# tp34.net
KiCad netlist of a schematic drawn in EAGLE
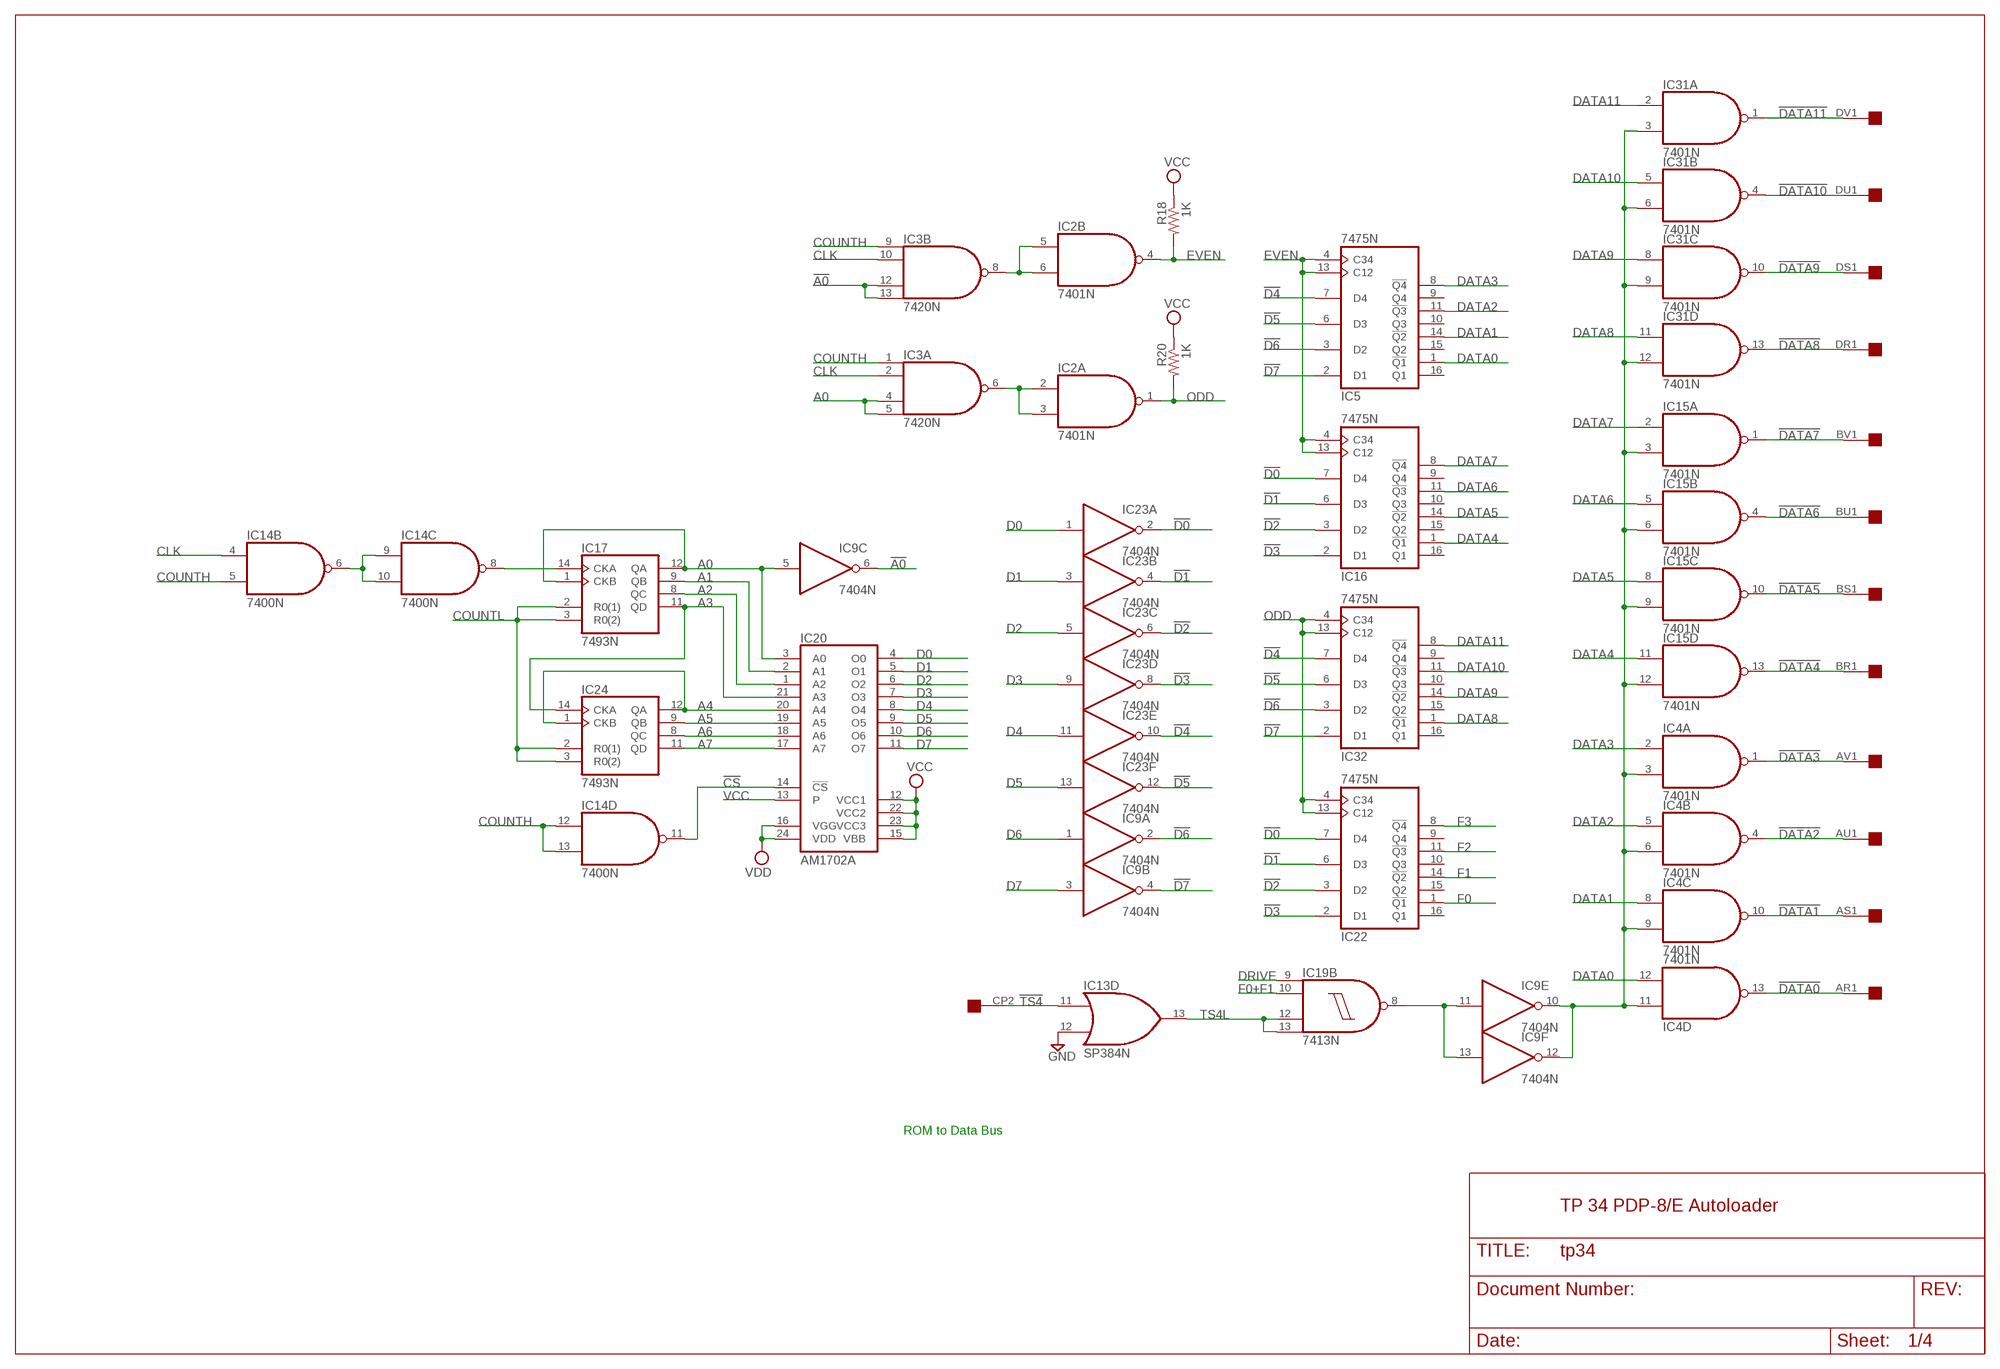
[diagram p0: schematic, sheet 1]
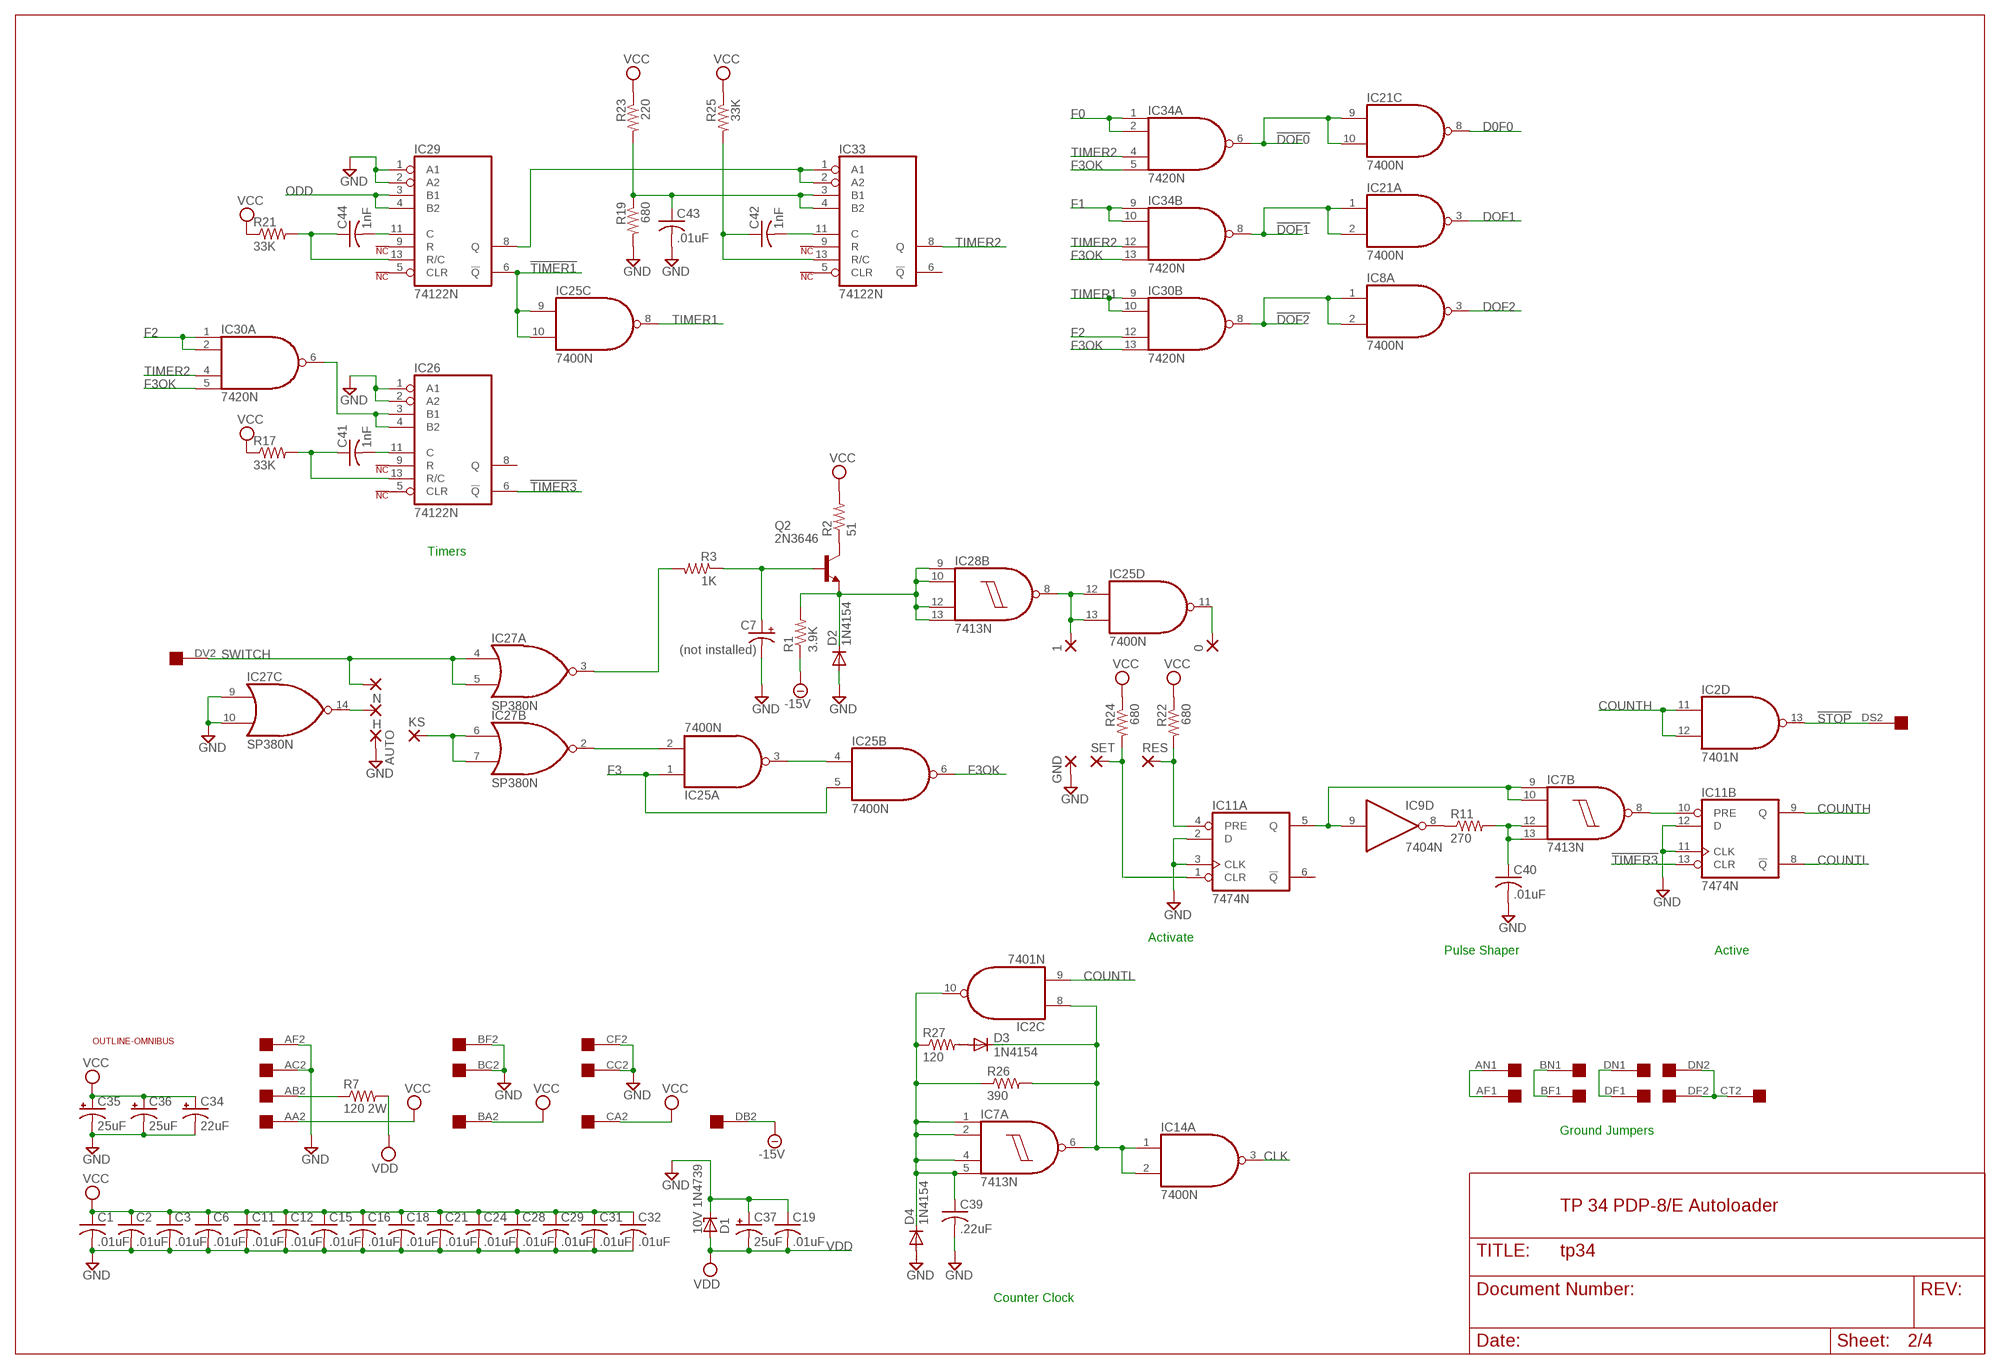
[diagram p1: schematic, sheet 2]
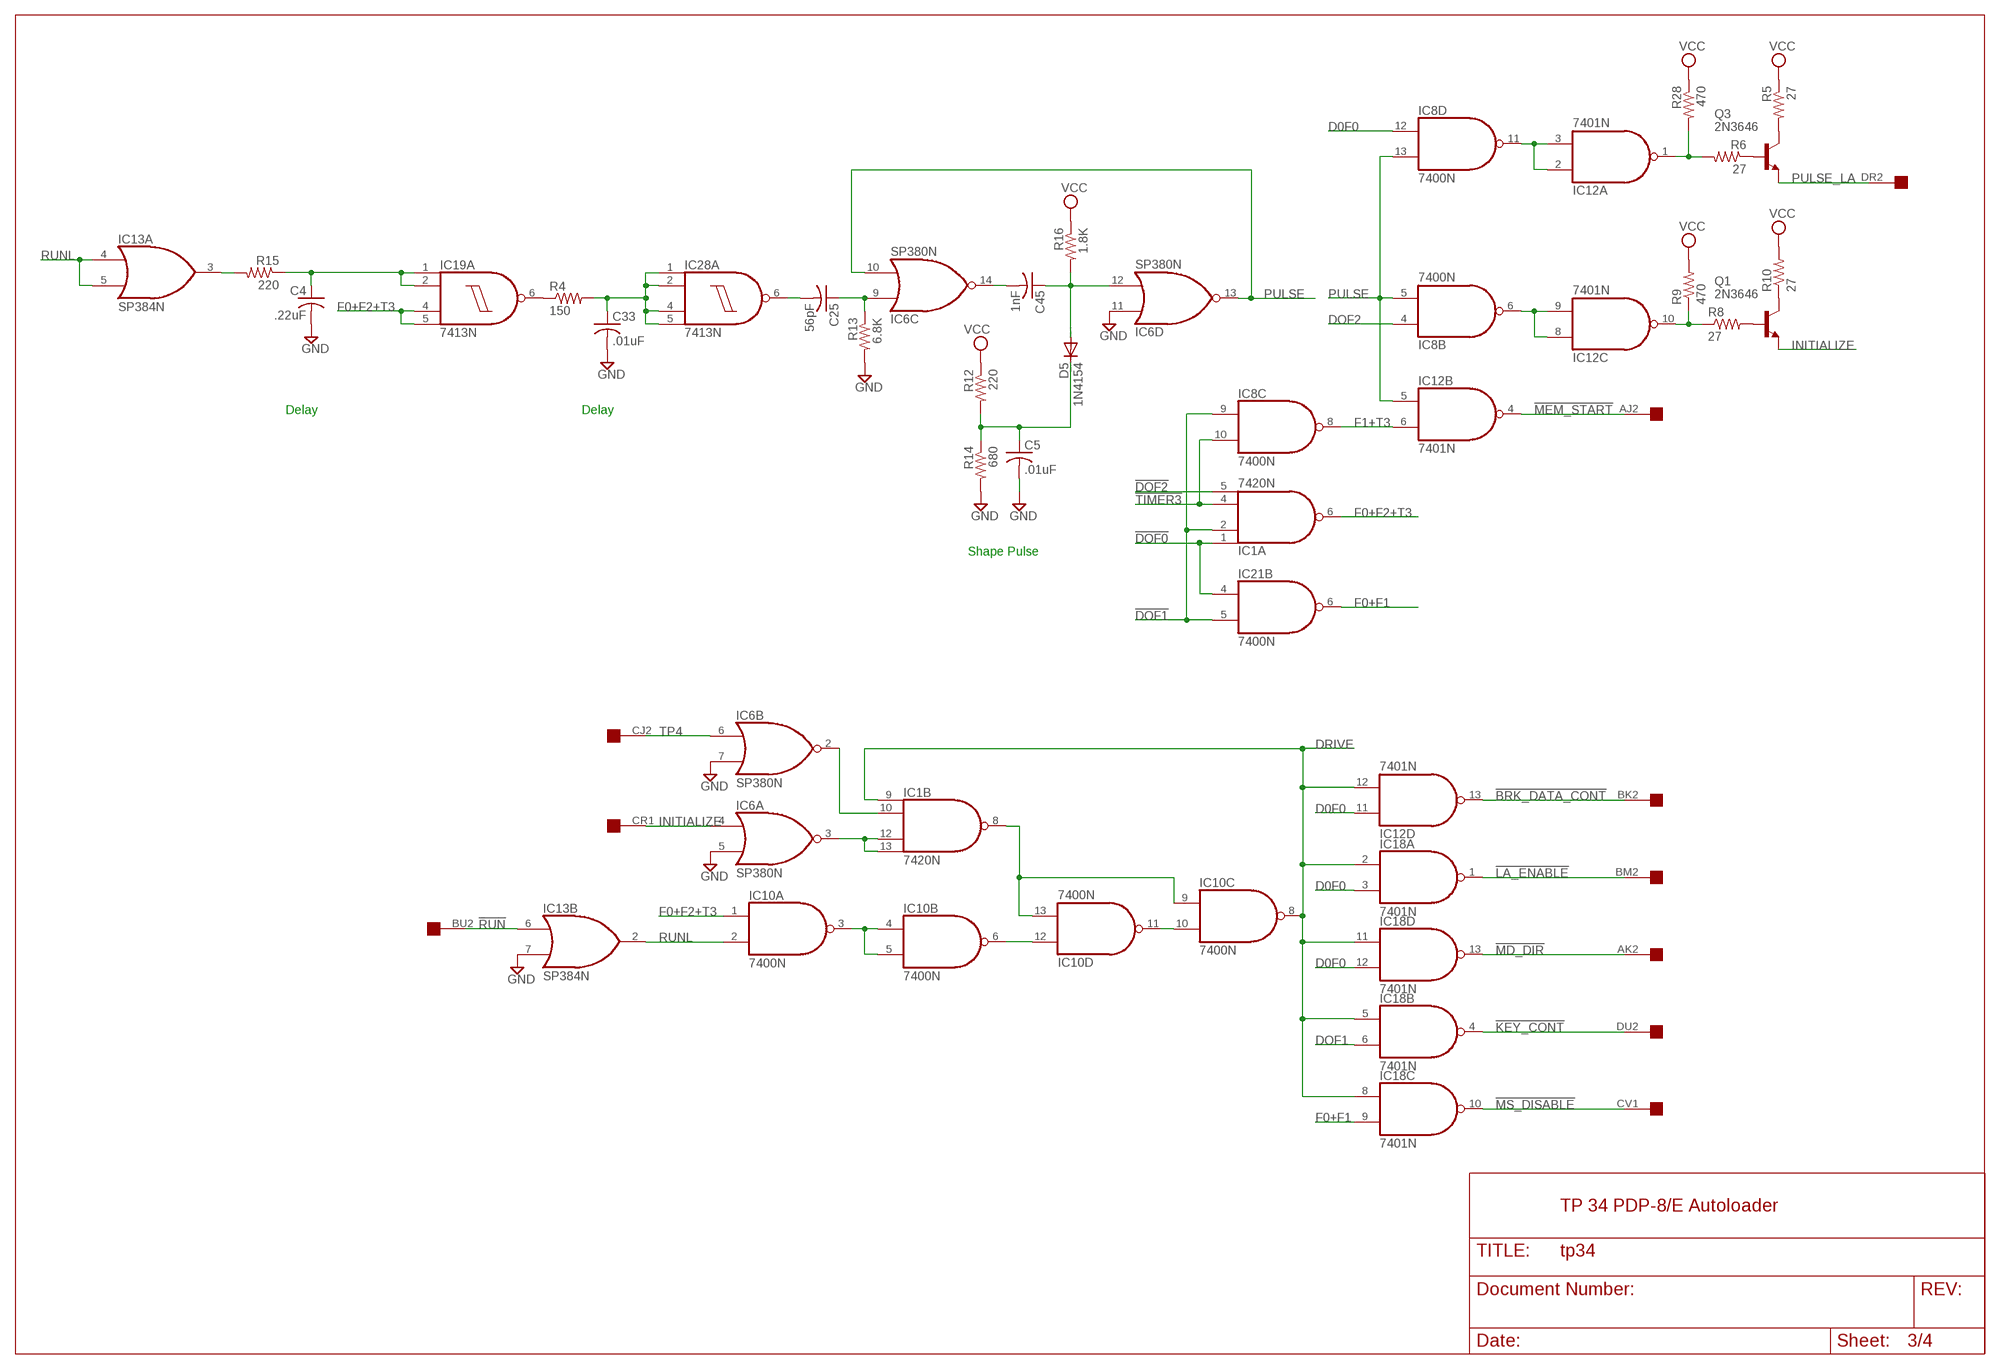
[diagram p2: schematic, sheet 3]
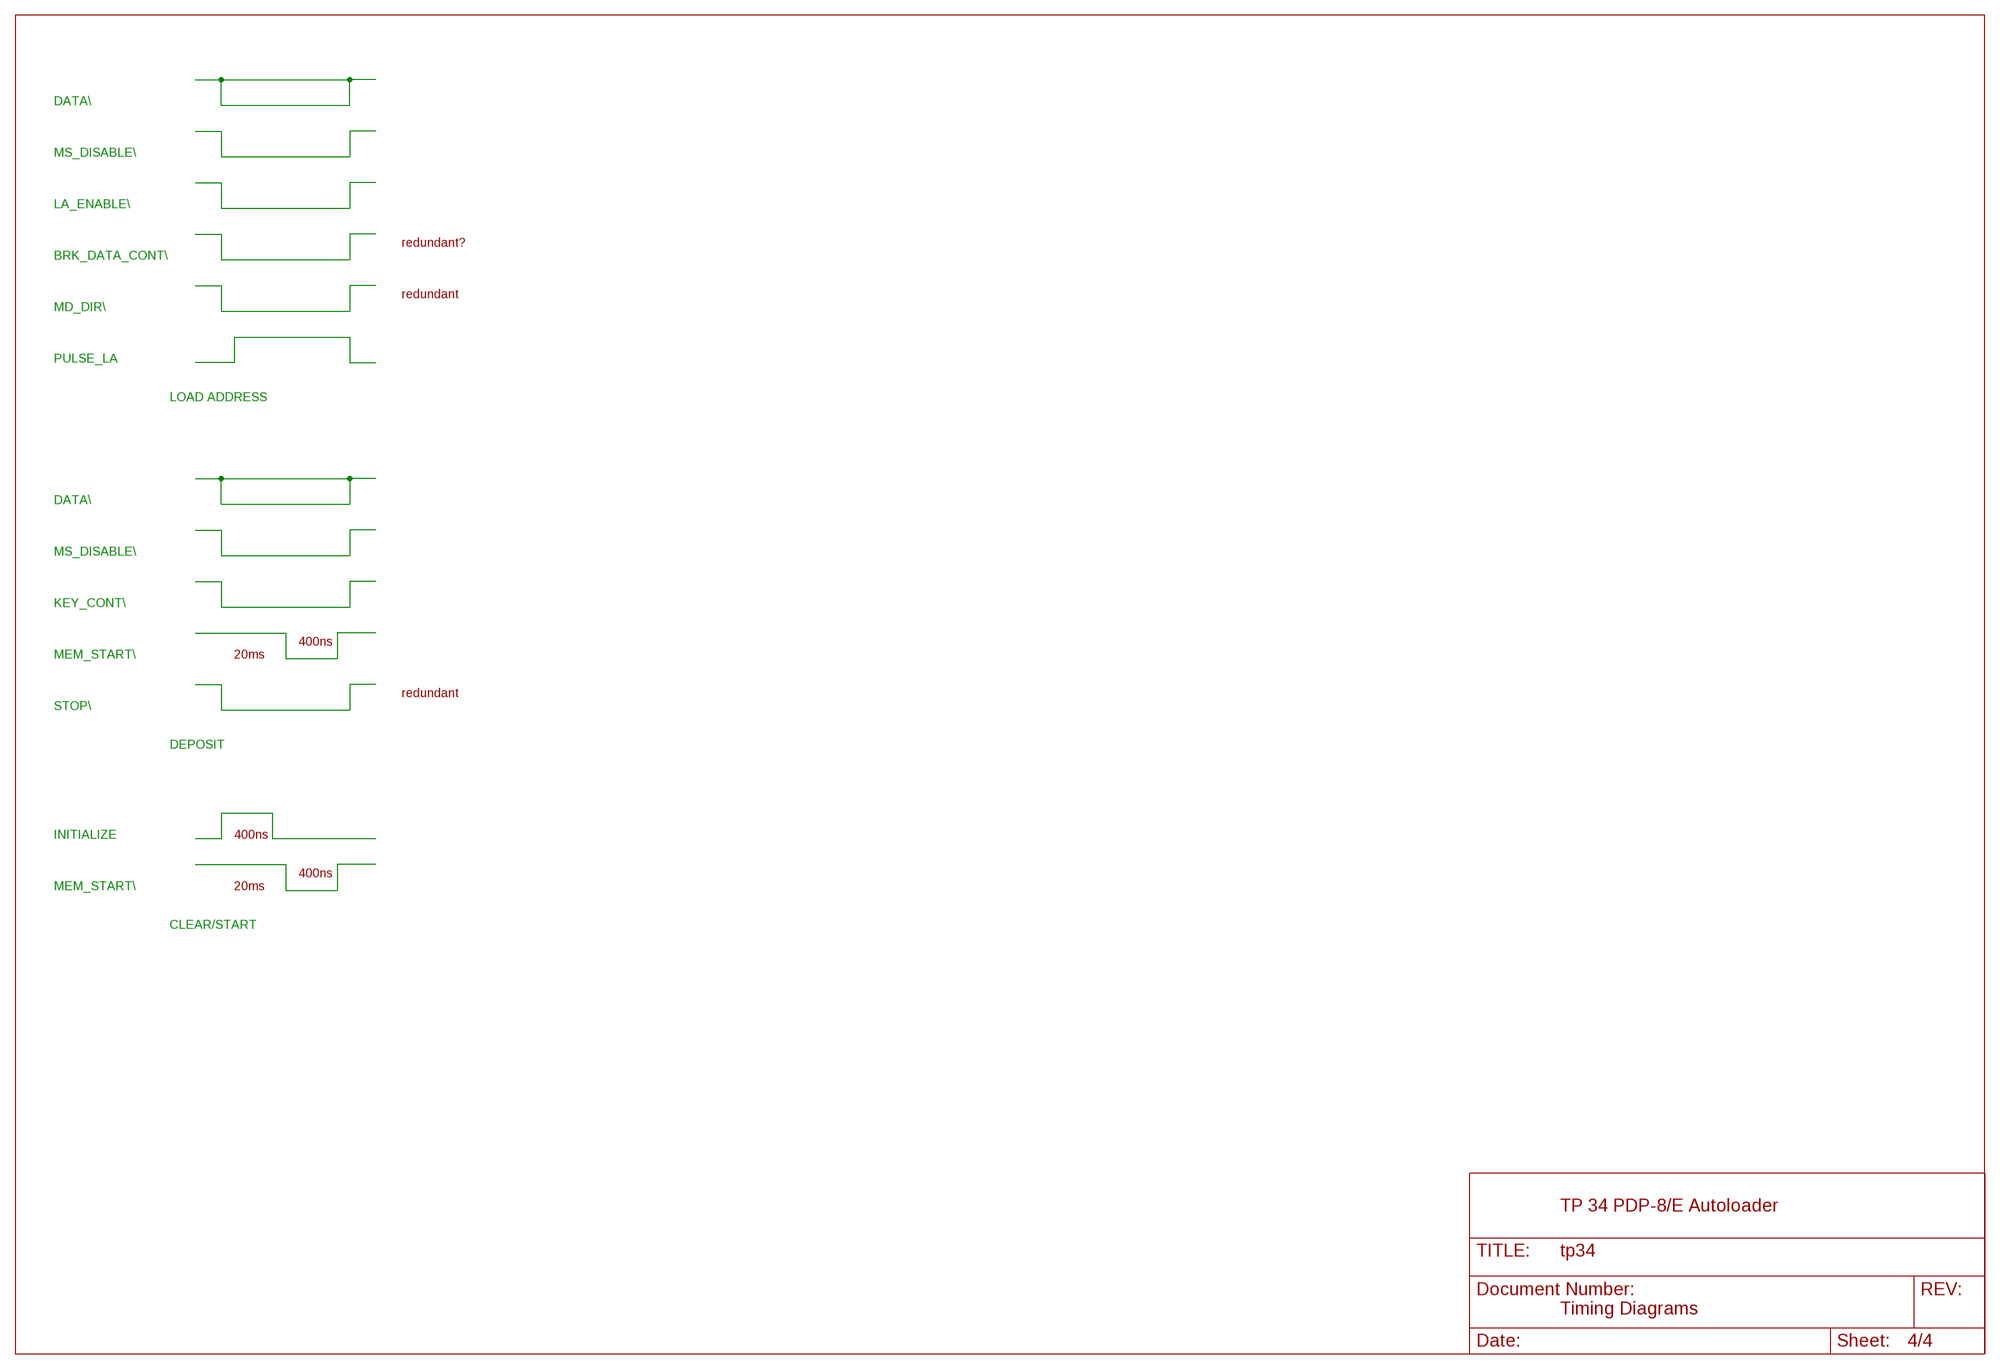
[diagram p3: schematic, sheet 4]

(export (version "E")
  (design (tool "Eeschema 10.0.6"))
  (components
    (comp (ref "IC2")
      (value "7401N")
      (footprint "eagle-import:DIL14")
      (libsource (lib "eagle-import") (part "7401NLS"))
    )
    (comp (ref "IC3")
      (value "7420N")
      (footprint "eagle-import:DIL14")
      (libsource (lib "eagle-import") (part "7420NS"))
    )
    (comp (ref "IC4")
      (value "7401N")
      (footprint "eagle-import:DIL14")
      (libsource (lib "eagle-import") (part "7401NLS"))
    )
    (comp (ref "IC5")
      (value "7475N")
      (footprint "eagle-import:DIL16")
      (libsource (lib "eagle-import") (part "7475N"))
    )
    (comp (ref "IC9")
      (value "7404N")
      (footprint "eagle-import:DIL14")
      (libsource (lib "eagle-import") (part "7404N"))
    )
    (comp (ref "IC13")
      (value "SP384N")
      (footprint "eagle-import:DIL14")
      (libsource (lib "eagle-import") (part "SP384N"))
    )
    (comp (ref "IC14")
      (value "7400N")
      (footprint "eagle-import:DIL14")
      (libsource (lib "eagle-import") (part "7400N"))
    )
    (comp (ref "IC15")
      (value "7401N")
      (footprint "eagle-import:DIL14")
      (libsource (lib "eagle-import") (part "7401NLS"))
    )
    (comp (ref "IC16")
      (value "7475N")
      (footprint "eagle-import:DIL16")
      (libsource (lib "eagle-import") (part "7475N"))
    )
    (comp (ref "IC17")
      (value "7493N")
      (footprint "eagle-import:DIL14")
      (libsource (lib "eagle-import") (part "7493NLS"))
    )
    (comp (ref "IC19")
      (value "7413N")
      (footprint "eagle-import:DIL14")
      (libsource (lib "eagle-import") (part "7413N"))
    )
    (comp (ref "IC20")
      (value "AM1702A")
      (footprint "eagle-import:DIL24")
      (libsource (lib "eagle-import") (part "AM1702"))
    )
    (comp (ref "IC22")
      (value "7475N")
      (footprint "eagle-import:DIL16")
      (libsource (lib "eagle-import") (part "7475N"))
    )
    (comp (ref "IC23")
      (value "7404N")
      (footprint "eagle-import:DIL14")
      (libsource (lib "eagle-import") (part "7404N"))
    )
    (comp (ref "IC24")
      (value "7493N")
      (footprint "eagle-import:DIL14")
      (libsource (lib "eagle-import") (part "7493NLS"))
    )
    (comp (ref "IC31")
      (value "7401N")
      (footprint "eagle-import:DIL14")
      (libsource (lib "eagle-import") (part "7401NLS"))
    )
    (comp (ref "IC32")
      (value "7475N")
      (footprint "eagle-import:DIL16")
      (libsource (lib "eagle-import") (part "7475N"))
    )
    (comp (ref "R18")
      (value "1K")
      (footprint "eagle-import:0207_10")
      (libsource (lib "eagle-import") (part "R-US_0207/10"))
    )
    (comp (ref "R20")
      (value "1K")
      (footprint "eagle-import:0207_10")
      (libsource (lib "eagle-import") (part "R-US_0207/10"))
    )
    (comp (ref "U$2")
      (value "QUAD")
      (footprint "eagle-import:EDGE-CON8")
      (libsource (lib "eagle-import") (part "QUAD"))
    )
    (comp (ref "C4")
      (value ".22uF")
      (footprint "eagle-import:C075-032X103")
      (libsource (lib "eagle-import") (part "C-US075-032X103"))
    )
    (comp (ref "C5")
      (value ".01uF")
      (footprint "eagle-import:C075-032X103")
      (libsource (lib "eagle-import") (part "C-US075-032X103"))
    )
    (comp (ref "C25")
      (value "56pF")
      (footprint "eagle-import:C102-043X133")
      (libsource (lib "eagle-import") (part "C-US102-043X133"))
    )
    (comp (ref "C33")
      (value ".01uF")
      (footprint "eagle-import:C075-032X103")
      (libsource (lib "eagle-import") (part "C-US075-032X103"))
    )
    (comp (ref "C45")
      (value "1nF")
      (footprint "eagle-import:C050-035X075")
      (libsource (lib "eagle-import") (part "C-US050-035X075"))
    )
    (comp (ref "D5")
      (value "1N4154")
      (footprint "eagle-import:DO35-10")
      (libsource (lib "eagle-import") (part "1N4148DO35-10"))
    )
    (comp (ref "IC1")
      (value "7420N")
      (footprint "eagle-import:DIL14")
      (libsource (lib "eagle-import") (part "7420NS"))
    )
    (comp (ref "IC6")
      (value "SP380N")
      (footprint "eagle-import:DIL14")
      (libsource (lib "eagle-import") (part "SP380N"))
    )
    (comp (ref "IC8")
      (value "7400N")
      (footprint "eagle-import:DIL14")
      (libsource (lib "eagle-import") (part "7400N"))
    )
    (comp (ref "IC10")
      (value "7400N")
      (footprint "eagle-import:DIL14")
      (libsource (lib "eagle-import") (part "7400N"))
    )
    (comp (ref "IC12")
      (value "7401N")
      (footprint "eagle-import:DIL14")
      (libsource (lib "eagle-import") (part "7401NLS"))
    )
    (comp (ref "IC18")
      (value "7401N")
      (footprint "eagle-import:DIL14")
      (libsource (lib "eagle-import") (part "7401NLS"))
    )
    (comp (ref "IC21")
      (value "7400N")
      (footprint "eagle-import:DIL14")
      (libsource (lib "eagle-import") (part "7400N"))
    )
    (comp (ref "IC28")
      (value "7413N")
      (footprint "eagle-import:DIL14")
      (libsource (lib "eagle-import") (part "7413N"))
    )
    (comp (ref "Q1")
      (value "2N3646")
      (footprint "eagle-import:TO5")
      (libsource (lib "eagle-import") (part "2N2102"))
    )
    (comp (ref "Q3")
      (value "2N3646")
      (footprint "eagle-import:TO5")
      (libsource (lib "eagle-import") (part "2N2102"))
    )
    (comp (ref "R4")
      (value "150")
      (footprint "eagle-import:0207_10")
      (libsource (lib "eagle-import") (part "R-US_0207/10"))
    )
    (comp (ref "R5")
      (value "27")
      (footprint "eagle-import:0207_10")
      (libsource (lib "eagle-import") (part "R-US_0207/10"))
    )
    (comp (ref "R6")
      (value "27")
      (footprint "eagle-import:0207_10")
      (libsource (lib "eagle-import") (part "R-US_0207/10"))
    )
    (comp (ref "R8")
      (value "27")
      (footprint "eagle-import:0207_10")
      (libsource (lib "eagle-import") (part "R-US_0207/10"))
    )
    (comp (ref "R9")
      (value "470")
      (footprint "eagle-import:0207_10")
      (libsource (lib "eagle-import") (part "R-US_0207/10"))
    )
    (comp (ref "R10")
      (value "27")
      (footprint "eagle-import:0207_10")
      (libsource (lib "eagle-import") (part "R-US_0207/10"))
    )
    (comp (ref "R12")
      (value "220")
      (footprint "eagle-import:0207_10")
      (libsource (lib "eagle-import") (part "R-US_0207/10"))
    )
    (comp (ref "R13")
      (value "6.8K")
      (footprint "eagle-import:0207_10")
      (libsource (lib "eagle-import") (part "R-US_0207/10"))
    )
    (comp (ref "R14")
      (value "680")
      (footprint "eagle-import:0207_10")
      (libsource (lib "eagle-import") (part "R-US_0207/10"))
    )
    (comp (ref "R15")
      (value "220")
      (footprint "eagle-import:0207_15")
      (libsource (lib "eagle-import") (part "R-US_0207/15"))
    )
    (comp (ref "R16")
      (value "1.8K")
      (footprint "eagle-import:0207_10")
      (libsource (lib "eagle-import") (part "R-US_0207/10"))
    )
    (comp (ref "R28")
      (value "470")
      (footprint "eagle-import:0207_10")
      (libsource (lib "eagle-import") (part "R-US_0207/10"))
    )
    (comp (ref "0")
      (value "1,6/0,8")
      (footprint "eagle-import:1,6_0,8")
      (libsource (lib "eagle-import") (part "1,6/0,8"))
    )
    (comp (ref "1")
      (value "1,6/0,8")
      (footprint "eagle-import:1,6_0,8")
      (libsource (lib "eagle-import") (part "1,6/0,8"))
    )
    (comp (ref "AUTO")
      (value "1,6/0,8")
      (footprint "eagle-import:1,6_0,8")
      (libsource (lib "eagle-import") (part "1,6/0,8"))
    )
    (comp (ref "C1")
      (value ".01uF")
      (footprint "eagle-import:C075-032X103")
      (libsource (lib "eagle-import") (part "C-US075-032X103"))
    )
    (comp (ref "C2")
      (value ".01uF")
      (footprint "eagle-import:C075-032X103")
      (libsource (lib "eagle-import") (part "C-US075-032X103"))
    )
    (comp (ref "C3")
      (value ".01uF")
      (footprint "eagle-import:C075-032X103")
      (libsource (lib "eagle-import") (part "C-US075-032X103"))
    )
    (comp (ref "C6")
      (value ".01uF")
      (footprint "eagle-import:C075-032X103")
      (libsource (lib "eagle-import") (part "C-US075-032X103"))
    )
    (comp (ref "C7")
      (value "(not installed)")
      (footprint "eagle-import:E15-5")
      (libsource (lib "eagle-import") (part "CPOL-USE15-5AXIAL"))
    )
    (comp (ref "C11")
      (value ".01uF")
      (footprint "eagle-import:C075-032X103")
      (libsource (lib "eagle-import") (part "C-US075-032X103"))
    )
    (comp (ref "C12")
      (value ".01uF")
      (footprint "eagle-import:C075-032X103")
      (libsource (lib "eagle-import") (part "C-US075-032X103"))
    )
    (comp (ref "C15")
      (value ".01uF")
      (footprint "eagle-import:C075-032X103")
      (libsource (lib "eagle-import") (part "C-US075-032X103"))
    )
    (comp (ref "C16")
      (value ".01uF")
      (footprint "eagle-import:C075-032X103")
      (libsource (lib "eagle-import") (part "C-US075-032X103"))
    )
    (comp (ref "C18")
      (value ".01uF")
      (footprint "eagle-import:C075-032X103")
      (libsource (lib "eagle-import") (part "C-US075-032X103"))
    )
    (comp (ref "C19")
      (value ".01uF")
      (footprint "eagle-import:C075-032X103")
      (libsource (lib "eagle-import") (part "C-US075-032X103"))
    )
    (comp (ref "C21")
      (value ".01uF")
      (footprint "eagle-import:C075-032X103")
      (libsource (lib "eagle-import") (part "C-US075-032X103"))
    )
    (comp (ref "C24")
      (value ".01uF")
      (footprint "eagle-import:C075-032X103")
      (libsource (lib "eagle-import") (part "C-US075-032X103"))
    )
    (comp (ref "C28")
      (value ".01uF")
      (footprint "eagle-import:C075-032X103")
      (libsource (lib "eagle-import") (part "C-US075-032X103"))
    )
    (comp (ref "C29")
      (value ".01uF")
      (footprint "eagle-import:C075-032X103")
      (libsource (lib "eagle-import") (part "C-US075-032X103"))
    )
    (comp (ref "C31")
      (value ".01uF")
      (footprint "eagle-import:C075-032X103")
      (libsource (lib "eagle-import") (part "C-US075-032X103"))
    )
    (comp (ref "C32")
      (value ".01uF")
      (footprint "eagle-import:C075-032X103")
      (libsource (lib "eagle-import") (part "C-US075-032X103"))
    )
    (comp (ref "C34")
      (value "22uF")
      (footprint "eagle-import:E12-8")
      (libsource (lib "eagle-import") (part "CPOL-USE20-8AXIAL"))
    )
    (comp (ref "C35")
      (value "25uF")
      (footprint "eagle-import:E15-5")
      (libsource (lib "eagle-import") (part "CPOL-USE15-5AXIAL"))
    )
    (comp (ref "C36")
      (value "25uF")
      (footprint "eagle-import:E15-5")
      (libsource (lib "eagle-import") (part "CPOL-USE15-5AXIAL"))
    )
    (comp (ref "C37")
      (value "25uF")
      (footprint "eagle-import:E15-5")
      (libsource (lib "eagle-import") (part "CPOL-USE15-5AXIAL"))
    )
    (comp (ref "C39")
      (value ".22uF")
      (footprint "eagle-import:C075-032X103")
      (libsource (lib "eagle-import") (part "C-US075-032X103"))
    )
    (comp (ref "C40")
      (value ".01uF")
      (footprint "eagle-import:C075-032X103")
      (libsource (lib "eagle-import") (part "C-US075-032X103"))
    )
    (comp (ref "C41")
      (value "1nF")
      (footprint "eagle-import:C075-032X103")
      (libsource (lib "eagle-import") (part "C-US075-032X103"))
    )
    (comp (ref "C42")
      (value "1nF")
      (footprint "eagle-import:C075-032X103")
      (libsource (lib "eagle-import") (part "C-US075-032X103"))
    )
    (comp (ref "C43")
      (value ".01uF")
      (footprint "eagle-import:C075-032X103")
      (libsource (lib "eagle-import") (part "C-US075-032X103"))
    )
    (comp (ref "C44")
      (value "1nF")
      (footprint "eagle-import:C075-032X103")
      (libsource (lib "eagle-import") (part "C-US075-032X103"))
    )
    (comp (ref "D1")
      (value "10V 1N4739")
      (footprint "eagle-import:C1702-15")
      (libsource (lib "eagle-import") (part "ZENER-DIODEC1702-15"))
    )
    (comp (ref "D2")
      (value "1N4154")
      (footprint "eagle-import:DO35-10")
      (libsource (lib "eagle-import") (part "1N4148DO35-10"))
    )
    (comp (ref "D3")
      (value "1N4154")
      (footprint "eagle-import:DO35-10")
      (libsource (lib "eagle-import") (part "1N4148DO35-10"))
    )
    (comp (ref "D4")
      (value "1N4154")
      (footprint "eagle-import:DO35-10")
      (libsource (lib "eagle-import") (part "1N4148DO35-10"))
    )
    (comp (ref "GND")
      (value "1,6/0,8")
      (footprint "eagle-import:1,6_0,8")
      (libsource (lib "eagle-import") (part "1,6/0,8"))
    )
    (comp (ref "H")
      (value "1,6/0,8")
      (footprint "eagle-import:1,6_0,8")
      (libsource (lib "eagle-import") (part "1,6/0,8"))
    )
    (comp (ref "IC7")
      (value "7413N")
      (footprint "eagle-import:DIL14")
      (libsource (lib "eagle-import") (part "7413N"))
    )
    (comp (ref "IC11")
      (value "7474N")
      (footprint "eagle-import:DIL14")
      (libsource (lib "eagle-import") (part "7474NS"))
    )
    (comp (ref "IC25")
      (value "7400N")
      (footprint "eagle-import:DIL14")
      (libsource (lib "eagle-import") (part "7400N"))
    )
    (comp (ref "IC26")
      (value "74122N")
      (footprint "eagle-import:DIL14")
      (libsource (lib "eagle-import") (part "74122NLS"))
    )
    (comp (ref "IC27")
      (value "SP380N")
      (footprint "eagle-import:DIL14")
      (libsource (lib "eagle-import") (part "SP380N"))
    )
    (comp (ref "IC29")
      (value "74122N")
      (footprint "eagle-import:DIL14")
      (libsource (lib "eagle-import") (part "74122NLS"))
    )
    (comp (ref "IC30")
      (value "7420N")
      (footprint "eagle-import:DIL14")
      (libsource (lib "eagle-import") (part "7420NS"))
    )
    (comp (ref "IC33")
      (value "74122N")
      (footprint "eagle-import:DIL14")
      (libsource (lib "eagle-import") (part "74122NLS"))
    )
    (comp (ref "IC34")
      (value "7420N")
      (footprint "eagle-import:DIL14")
      (libsource (lib "eagle-import") (part "7420NS"))
    )
    (comp (ref "KS")
      (value "1,6/0,8")
      (footprint "eagle-import:1,6_0,8")
      (libsource (lib "eagle-import") (part "1,6/0,8"))
    )
    (comp (ref "N")
      (value "1,6/0,8")
      (footprint "eagle-import:1,6_0,8")
      (libsource (lib "eagle-import") (part "1,6/0,8"))
    )
    (comp (ref "Q2")
      (value "2N3646")
      (footprint "eagle-import:TO5")
      (libsource (lib "eagle-import") (part "2N2102"))
    )
    (comp (ref "R1")
      (value "3.9K")
      (footprint "eagle-import:0207_10")
      (libsource (lib "eagle-import") (part "R-US_0207/10"))
    )
    (comp (ref "R2")
      (value "51")
      (footprint "eagle-import:0207_10")
      (libsource (lib "eagle-import") (part "R-US_0207/10"))
    )
    (comp (ref "R3")
      (value "1K")
      (footprint "eagle-import:0207_10")
      (libsource (lib "eagle-import") (part "R-US_0207/10"))
    )
    (comp (ref "R7")
      (value "120 2W")
      (footprint "eagle-import:0414_15")
      (libsource (lib "eagle-import") (part "R-US_0414/15"))
    )
    (comp (ref "R11")
      (value "270")
      (footprint "eagle-import:0207_12")
      (libsource (lib "eagle-import") (part "R-US_0207/12"))
    )
    (comp (ref "R17")
      (value "33K")
      (footprint "eagle-import:0207_10")
      (libsource (lib "eagle-import") (part "R-US_0207/10"))
    )
    (comp (ref "R19")
      (value "680")
      (footprint "eagle-import:0207_10")
      (libsource (lib "eagle-import") (part "R-US_0207/10"))
    )
    (comp (ref "R21")
      (value "33K")
      (footprint "eagle-import:0207_10")
      (libsource (lib "eagle-import") (part "R-US_0207/10"))
    )
    (comp (ref "R22")
      (value "680")
      (footprint "eagle-import:0207_10")
      (libsource (lib "eagle-import") (part "R-US_0207/10"))
    )
    (comp (ref "R23")
      (value "220")
      (footprint "eagle-import:0207_10")
      (libsource (lib "eagle-import") (part "R-US_0207/10"))
    )
    (comp (ref "R24")
      (value "680")
      (footprint "eagle-import:0207_10")
      (libsource (lib "eagle-import") (part "R-US_0207/10"))
    )
    (comp (ref "R25")
      (value "33K")
      (footprint "eagle-import:0207_10")
      (libsource (lib "eagle-import") (part "R-US_0207/10"))
    )
    (comp (ref "R26")
      (value "390")
      (footprint "eagle-import:0207_10")
      (libsource (lib "eagle-import") (part "R-US_0207/10"))
    )
    (comp (ref "R27")
      (value "120")
      (footprint "eagle-import:0207_10")
      (libsource (lib "eagle-import") (part "R-US_0207/10"))
    )
    (comp (ref "RES")
      (value "1,6/0,8")
      (footprint "eagle-import:1,6_0,8")
      (libsource (lib "eagle-import") (part "1,6/0,8"))
    )
    (comp (ref "SET")
      (value "1,6/0,8")
      (footprint "eagle-import:1,6_0,8")
      (libsource (lib "eagle-import") (part "1,6/0,8"))
    )
    (comp (ref "U$1")
      (value "OUTLINE-OMNIBUS")
      (footprint "eagle-import:OMNIBUS")
      (libsource (lib "eagle-import") (part "OUTLINE-OMNIBUS"))
    )
  )
  (nets
    (net (code "1") (name "-15V") (class "Default")
      (node (ref "R1") (pin "1") (pinfunction "1_1") (pintype "passive"))
      (node (ref "U$2") (pin "DB2") (pinfunction "1_DB2") (pintype "bidirectional"))
    )
    (net (code "2") (name "A0") (class "Default")
      (node (ref "IC17") (pin "1") (pinfunction "CKB_1") (pintype "input"))
      (node (ref "IC17") (pin "12") (pinfunction "QA_12") (pintype "output"))
      (node (ref "IC20") (pin "3") (pinfunction "A0_3") (pintype "input"))
      (node (ref "IC3") (pin "4") (pinfunction "I2_4") (pintype "input"))
      (node (ref "IC3") (pin "5") (pinfunction "I3_5") (pintype "input"))
      (node (ref "IC9") (pin "5") (pinfunction "I_5") (pintype "input"))
    )
    (net (code "3") (name "A1") (class "Default")
      (node (ref "IC17") (pin "9") (pinfunction "QB_9") (pintype "output"))
      (node (ref "IC20") (pin "2") (pinfunction "A1_2") (pintype "input"))
    )
    (net (code "4") (name "A2") (class "Default")
      (node (ref "IC17") (pin "8") (pinfunction "QC_8") (pintype "output"))
      (node (ref "IC20") (pin "1") (pinfunction "A2_1") (pintype "input"))
    )
    (net (code "5") (name "A3") (class "Default")
      (node (ref "IC17") (pin "11") (pinfunction "QD_11") (pintype "output"))
      (node (ref "IC20") (pin "21") (pinfunction "A3_21") (pintype "input"))
      (node (ref "IC24") (pin "14") (pinfunction "CKA_14") (pintype "input"))
    )
    (net (code "6") (name "A4") (class "Default")
      (node (ref "IC20") (pin "20") (pinfunction "A4_20") (pintype "input"))
      (node (ref "IC24") (pin "1") (pinfunction "CKB_1") (pintype "input"))
      (node (ref "IC24") (pin "12") (pinfunction "QA_12") (pintype "output"))
    )
    (net (code "7") (name "A5") (class "Default")
      (node (ref "IC20") (pin "19") (pinfunction "A5_19") (pintype "input"))
      (node (ref "IC24") (pin "9") (pinfunction "QB_9") (pintype "output"))
    )
    (net (code "8") (name "A6") (class "Default")
      (node (ref "IC20") (pin "18") (pinfunction "A6_18") (pintype "input"))
      (node (ref "IC24") (pin "8") (pinfunction "QC_8") (pintype "output"))
    )
    (net (code "9") (name "A7") (class "Default")
      (node (ref "IC20") (pin "17") (pinfunction "A7_17") (pintype "input"))
      (node (ref "IC24") (pin "11") (pinfunction "QD_11") (pintype "output"))
    )
    (net (code "10") (name "CLK") (class "Default")
      (node (ref "IC14") (pin "3") (pinfunction "O_3") (pintype "output"))
      (node (ref "IC14") (pin "4") (pinfunction "I0_4") (pintype "input"))
      (node (ref "IC3") (pin "10") (pinfunction "I1_10") (pintype "input"))
      (node (ref "IC3") (pin "2") (pinfunction "I1_2") (pintype "input"))
    )
    (net (code "11") (name "COUNTH") (class "Default")
      (node (ref "IC11") (pin "9") (pinfunction "Q_9") (pintype "output"))
      (node (ref "IC14") (pin "12") (pinfunction "I0_12") (pintype "input"))
      (node (ref "IC14") (pin "13") (pinfunction "I1_13") (pintype "input"))
      (node (ref "IC14") (pin "5") (pinfunction "I1_5") (pintype "input"))
      (node (ref "IC2") (pin "11") (pinfunction "I0_11") (pintype "input"))
      (node (ref "IC2") (pin "12") (pinfunction "I1_12") (pintype "input"))
      (node (ref "IC3") (pin "1") (pinfunction "I0_1") (pintype "input"))
      (node (ref "IC3") (pin "9") (pinfunction "I0_9") (pintype "input"))
    )
    (net (code "12") (name "COUNTL") (class "Default")
      (node (ref "IC11") (pin "8") (pinfunction "~{Q}_8") (pintype "output"))
      (node (ref "IC17") (pin "2") (pinfunction "R0(1)_2") (pintype "input"))
      (node (ref "IC17") (pin "3") (pinfunction "R0(2)_3") (pintype "input"))
      (node (ref "IC2") (pin "9") (pinfunction "I1_9") (pintype "input"))
      (node (ref "IC24") (pin "2") (pinfunction "R0(1)_2") (pintype "input"))
      (node (ref "IC24") (pin "3") (pinfunction "R0(2)_3") (pintype "input"))
    )
    (net (code "13") (name "D0") (class "Default")
      (node (ref "IC20") (pin "4") (pinfunction "O0_4") (pintype "tri_state"))
      (node (ref "IC23") (pin "1") (pinfunction "I_1") (pintype "input"))
    )
    (net (code "14") (name "D0F0") (class "Default")
      (node (ref "IC12") (pin "11") (pinfunction "I0_11") (pintype "input"))
      (node (ref "IC18") (pin "12") (pinfunction "I1_12") (pintype "input"))
      (node (ref "IC18") (pin "3") (pinfunction "I1_3") (pintype "input"))
      (node (ref "IC21") (pin "8") (pinfunction "O_8") (pintype "output"))
      (node (ref "IC8") (pin "12") (pinfunction "I0_12") (pintype "input"))
    )
    (net (code "15") (name "D1") (class "Default")
      (node (ref "IC20") (pin "5") (pinfunction "O1_5") (pintype "tri_state"))
      (node (ref "IC23") (pin "3") (pinfunction "I_3") (pintype "input"))
    )
    (net (code "16") (name "D2") (class "Default")
      (node (ref "IC20") (pin "6") (pinfunction "O2_6") (pintype "tri_state"))
      (node (ref "IC23") (pin "5") (pinfunction "I_5") (pintype "input"))
    )
    (net (code "17") (name "D3") (class "Default")
      (node (ref "IC20") (pin "7") (pinfunction "O3_7") (pintype "tri_state"))
      (node (ref "IC23") (pin "9") (pinfunction "I_9") (pintype "input"))
    )
    (net (code "18") (name "D4") (class "Default")
      (node (ref "IC20") (pin "8") (pinfunction "O4_8") (pintype "tri_state"))
      (node (ref "IC23") (pin "11") (pinfunction "I_11") (pintype "input"))
    )
    (net (code "19") (name "D5") (class "Default")
      (node (ref "IC20") (pin "9") (pinfunction "O5_9") (pintype "tri_state"))
      (node (ref "IC23") (pin "13") (pinfunction "I_13") (pintype "input"))
    )
    (net (code "20") (name "D6") (class "Default")
      (node (ref "IC20") (pin "10") (pinfunction "O6_10") (pintype "tri_state"))
      (node (ref "IC9") (pin "1") (pinfunction "I_1") (pintype "input"))
    )
    (net (code "21") (name "D7") (class "Default")
      (node (ref "IC20") (pin "11") (pinfunction "O7_11") (pintype "tri_state"))
      (node (ref "IC9") (pin "3") (pinfunction "I_3") (pintype "input"))
    )
    (net (code "22") (name "DATA0") (class "Default")
      (node (ref "IC4") (pin "12") (pinfunction "I1_12") (pintype "input"))
      (node (ref "IC5") (pin "1") (pinfunction "~{Q1}_1") (pintype "output"))
    )
    (net (code "23") (name "DATA1") (class "Default")
      (node (ref "IC4") (pin "8") (pinfunction "I0_8") (pintype "input"))
      (node (ref "IC5") (pin "14") (pinfunction "~{Q2}_14") (pintype "output"))
    )
    (net (code "24") (name "DATA2") (class "Default")
      (node (ref "IC4") (pin "5") (pinfunction "I0_5") (pintype "input"))
      (node (ref "IC5") (pin "11") (pinfunction "~{Q3}_11") (pintype "output"))
    )
    (net (code "25") (name "DATA3") (class "Default")
      (node (ref "IC4") (pin "2") (pinfunction "I0_2") (pintype "input"))
      (node (ref "IC5") (pin "8") (pinfunction "~{Q4}_8") (pintype "output"))
    )
    (net (code "26") (name "DATA4") (class "Default")
      (node (ref "IC15") (pin "11") (pinfunction "I0_11") (pintype "input"))
      (node (ref "IC16") (pin "1") (pinfunction "~{Q1}_1") (pintype "output"))
    )
    (net (code "27") (name "DATA5") (class "Default")
      (node (ref "IC15") (pin "8") (pinfunction "I0_8") (pintype "input"))
      (node (ref "IC16") (pin "14") (pinfunction "~{Q2}_14") (pintype "output"))
    )
    (net (code "28") (name "DATA6") (class "Default")
      (node (ref "IC15") (pin "5") (pinfunction "I0_5") (pintype "input"))
      (node (ref "IC16") (pin "11") (pinfunction "~{Q3}_11") (pintype "output"))
    )
    (net (code "29") (name "DATA7") (class "Default")
      (node (ref "IC15") (pin "2") (pinfunction "I0_2") (pintype "input"))
      (node (ref "IC16") (pin "8") (pinfunction "~{Q4}_8") (pintype "output"))
    )
    (net (code "30") (name "DATA8") (class "Default")
      (node (ref "IC31") (pin "11") (pinfunction "I0_11") (pintype "input"))
      (node (ref "IC32") (pin "1") (pinfunction "~{Q1}_1") (pintype "output"))
    )
    (net (code "31") (name "DATA9") (class "Default")
      (node (ref "IC31") (pin "8") (pinfunction "I0_8") (pintype "input"))
      (node (ref "IC32") (pin "14") (pinfunction "~{Q2}_14") (pintype "output"))
    )
    (net (code "32") (name "DATA10") (class "Default")
      (node (ref "IC31") (pin "5") (pinfunction "I0_5") (pintype "input"))
      (node (ref "IC32") (pin "11") (pinfunction "~{Q3}_11") (pintype "output"))
    )
    (net (code "33") (name "DATA11") (class "Default")
      (node (ref "IC31") (pin "2") (pinfunction "I0_2") (pintype "input"))
      (node (ref "IC32") (pin "8") (pinfunction "~{Q4}_8") (pintype "output"))
    )
    (net (code "34") (name "DOF1") (class "Default")
      (node (ref "IC18") (pin "6") (pinfunction "I1_6") (pintype "input"))
      (node (ref "IC21") (pin "3") (pinfunction "O_3") (pintype "output"))
    )
    (net (code "35") (name "DOF2") (class "Default")
      (node (ref "IC8") (pin "3") (pinfunction "O_3") (pintype "output"))
      (node (ref "IC8") (pin "4") (pinfunction "I0_4") (pintype "input"))
    )
    (net (code "36") (name "DRIVE") (class "Default")
      (node (ref "IC1") (pin "9") (pinfunction "I0_9") (pintype "input"))
      (node (ref "IC10") (pin "8") (pinfunction "O_8") (pintype "output"))
      (node (ref "IC12") (pin "12") (pinfunction "I1_12") (pintype "input"))
      (node (ref "IC18") (pin "11") (pinfunction "I0_11") (pintype "input"))
      (node (ref "IC18") (pin "2") (pinfunction "I0_2") (pintype "input"))
      (node (ref "IC18") (pin "5") (pinfunction "I0_5") (pintype "input"))
      (node (ref "IC18") (pin "8") (pinfunction "I0_8") (pintype "input"))
      (node (ref "IC19") (pin "9") (pinfunction "I0_9") (pintype "input"))
    )
    (net (code "37") (name "EVEN") (class "Default")
      (node (ref "IC16") (pin "13") (pinfunction "C12_13") (pintype "input"))
      (node (ref "IC16") (pin "4") (pinfunction "C34_4") (pintype "input"))
      (node (ref "IC2") (pin "4") (pinfunction "O_4") (pintype "open_collector"))
      (node (ref "IC5") (pin "13") (pinfunction "C12_13") (pintype "input"))
      (node (ref "IC5") (pin "4") (pinfunction "C34_4") (pintype "input"))
      (node (ref "R18") (pin "2") (pinfunction "2_2") (pintype "passive"))
    )
    (net (code "38") (name "F0") (class "Default")
      (node (ref "IC22") (pin "1") (pinfunction "~{Q1}_1") (pintype "output"))
      (node (ref "IC34") (pin "1") (pinfunction "I0_1") (pintype "input"))
      (node (ref "IC34") (pin "2") (pinfunction "I1_2") (pintype "input"))
    )
    (net (code "39") (name "F0+F1") (class "Default")
      (node (ref "IC18") (pin "9") (pinfunction "I1_9") (pintype "input"))
      (node (ref "IC19") (pin "10") (pinfunction "I1_10") (pintype "input"))
      (node (ref "IC21") (pin "6") (pinfunction "O_6") (pintype "output"))
    )
    (net (code "40") (name "F0+F2+T3") (class "Default")
      (node (ref "IC1") (pin "6") (pinfunction "O_6") (pintype "output"))
      (node (ref "IC10") (pin "1") (pinfunction "I0_1") (pintype "input"))
      (node (ref "IC19") (pin "4") (pinfunction "I2_4") (pintype "input"))
      (node (ref "IC19") (pin "5") (pinfunction "I3_5") (pintype "input"))
    )
    (net (code "41") (name "F1") (class "Default")
      (node (ref "IC22") (pin "14") (pinfunction "~{Q2}_14") (pintype "output"))
      (node (ref "IC34") (pin "10") (pinfunction "I1_10") (pintype "input"))
      (node (ref "IC34") (pin "9") (pinfunction "I0_9") (pintype "input"))
    )
    (net (code "42") (name "F1+T3") (class "Default")
      (node (ref "IC12") (pin "6") (pinfunction "I1_6") (pintype "input"))
      (node (ref "IC8") (pin "8") (pinfunction "O_8") (pintype "output"))
    )
    (net (code "43") (name "F2") (class "Default")
      (node (ref "IC22") (pin "11") (pinfunction "~{Q3}_11") (pintype "output"))
      (node (ref "IC30") (pin "1") (pinfunction "I0_1") (pintype "input"))
      (node (ref "IC30") (pin "12") (pinfunction "I2_12") (pintype "input"))
      (node (ref "IC30") (pin "2") (pinfunction "I1_2") (pintype "input"))
    )
    (net (code "44") (name "F3") (class "Default")
      (node (ref "IC22") (pin "8") (pinfunction "~{Q4}_8") (pintype "output"))
      (node (ref "IC25") (pin "1") (pinfunction "I0_1") (pintype "input"))
      (node (ref "IC25") (pin "5") (pinfunction "I1_5") (pintype "input"))
    )
    (net (code "45") (name "F3OK") (class "Default")
      (node (ref "IC25") (pin "6") (pinfunction "O_6") (pintype "output"))
      (node (ref "IC30") (pin "13") (pinfunction "I3_13") (pintype "input"))
      (node (ref "IC30") (pin "5") (pinfunction "I3_5") (pintype "input"))
      (node (ref "IC34") (pin "13") (pinfunction "I3_13") (pintype "input"))
      (node (ref "IC34") (pin "5") (pinfunction "I3_5") (pintype "input"))
    )
    (net (code "46") (name "GND") (class "Default")
      (node (ref "AUTO") (pin "1") (pinfunction "P_1") (pintype "passive"))
      (node (ref "C1") (pin "2") (pinfunction "2_2") (pintype "passive"))
      (node (ref "C11") (pin "2") (pinfunction "2_2") (pintype "passive"))
      (node (ref "C12") (pin "2") (pinfunction "2_2") (pintype "passive"))
      (node (ref "C15") (pin "2") (pinfunction "2_2") (pintype "passive"))
      (node (ref "C16") (pin "2") (pinfunction "2_2") (pintype "passive"))
      (node (ref "C18") (pin "2") (pinfunction "2_2") (pintype "passive"))
      (node (ref "C19") (pin "1") (pinfunction "1_1") (pintype "passive"))
      (node (ref "C2") (pin "2") (pinfunction "2_2") (pintype "passive"))
      (node (ref "C21") (pin "2") (pinfunction "2_2") (pintype "passive"))
      (node (ref "C24") (pin "2") (pinfunction "2_2") (pintype "passive"))
      (node (ref "C28") (pin "2") (pinfunction "2_2") (pintype "passive"))
      (node (ref "C29") (pin "2") (pinfunction "2_2") (pintype "passive"))
      (node (ref "C3") (pin "2") (pinfunction "2_2") (pintype "passive"))
      (node (ref "C31") (pin "2") (pinfunction "2_2") (pintype "passive"))
      (node (ref "C32") (pin "2") (pinfunction "2_2") (pintype "passive"))
      (node (ref "C33") (pin "2") (pinfunction "2_2") (pintype "passive"))
      (node (ref "C34") (pin "-") (pinfunction "-_-") (pintype "passive"))
      (node (ref "C35") (pin "-") (pinfunction "-_-") (pintype "passive"))
      (node (ref "C36") (pin "-") (pinfunction "-_-") (pintype "passive"))
      (node (ref "C37") (pin "+") (pinfunction "+_+") (pintype "passive"))
      (node (ref "C39") (pin "2") (pinfunction "2_2") (pintype "passive"))
      (node (ref "C4") (pin "2") (pinfunction "2_2") (pintype "passive"))
      (node (ref "C40") (pin "2") (pinfunction "2_2") (pintype "passive"))
      (node (ref "C43") (pin "2") (pinfunction "2_2") (pintype "passive"))
      (node (ref "C5") (pin "2") (pinfunction "2_2") (pintype "passive"))
      (node (ref "C6") (pin "2") (pinfunction "2_2") (pintype "passive"))
      (node (ref "C7") (pin "-") (pinfunction "-_-") (pintype "passive"))
      (node (ref "D1") (pin "C") (pinfunction "C_C") (pintype "passive"))
      (node (ref "D2") (pin "A") (pinfunction "A_A") (pintype "passive"))
      (node (ref "D4") (pin "A") (pinfunction "A_A") (pintype "passive"))
      (node (ref "GND") (pin "1") (pinfunction "P_1") (pintype "passive"))
      (node (ref "IC11") (pin "11") (pinfunction "CLK_11") (pintype "input"))
      (node (ref "IC11") (pin "12") (pinfunction "D_12") (pintype "input"))
      (node (ref "IC11") (pin "2") (pinfunction "D_2") (pintype "input"))
      (node (ref "IC11") (pin "3") (pinfunction "CLK_3") (pintype "input"))
      (node (ref "IC13") (pin "12") (pinfunction "I1_12") (pintype "input"))
      (node (ref "IC13") (pin "7") (pinfunction "I1_7") (pintype "input"))
      (node (ref "IC26") (pin "1") (pinfunction "A1_1") (pintype "input"))
      (node (ref "IC26") (pin "2") (pinfunction "A2_2") (pintype "input"))
      (node (ref "IC27") (pin "10") (pinfunction "I1_10") (pintype "input"))
      (node (ref "IC27") (pin "9") (pinfunction "I0_9") (pintype "input"))
      (node (ref "IC29") (pin "1") (pinfunction "A1_1") (pintype "input"))
      (node (ref "IC29") (pin "2") (pinfunction "A2_2") (pintype "input"))
      (node (ref "IC6") (pin "11") (pinfunction "I0_11") (pintype "input"))
      (node (ref "IC6") (pin "5") (pinfunction "I1_5") (pintype "input"))
      (node (ref "IC6") (pin "7") (pinfunction "I1_7") (pintype "input"))
      (node (ref "R13") (pin "2") (pinfunction "2_2") (pintype "passive"))
      (node (ref "R14") (pin "2") (pinfunction "2_2") (pintype "passive"))
      (node (ref "R19") (pin "2") (pinfunction "2_2") (pintype "passive"))
      (node (ref "U$2") (pin "AC2") (pinfunction "1_AC2") (pintype "bidirectional"))
      (node (ref "U$2") (pin "AF2") (pinfunction "1_AF2") (pintype "bidirectional"))
      (node (ref "U$2") (pin "BC2") (pinfunction "1_BC2") (pintype "bidirectional"))
      (node (ref "U$2") (pin "BF2") (pinfunction "1_BF2") (pintype "bidirectional"))
      (node (ref "U$2") (pin "CC2") (pinfunction "1_CC2") (pintype "bidirectional"))
      (node (ref "U$2") (pin "CF2") (pinfunction "1_CF2") (pintype "bidirectional"))
    )
    (net (code "47") (name "INITIALIZE") (class "Default")
      (node (ref "IC6") (pin "4") (pinfunction "I0_4") (pintype "input"))
      (node (ref "Q1") (pin "1") (pinfunction "E_1") (pintype "passive"))
      (node (ref "U$2") (pin "CR1") (pinfunction "1_CR1") (pintype "bidirectional"))
    )
    (net (code "48") (name "NC") (class "Default")
      (node (ref "IC26") (pin "5") (pinfunction "CLR_5") (pintype "input"))
      (node (ref "IC26") (pin "9") (pinfunction "R_9") (pintype "input"))
      (node (ref "IC29") (pin "5") (pinfunction "CLR_5") (pintype "input"))
      (node (ref "IC29") (pin "9") (pinfunction "R_9") (pintype "input"))
      (node (ref "IC33") (pin "5") (pinfunction "CLR_5") (pintype "input"))
      (node (ref "IC33") (pin "9") (pinfunction "R_9") (pintype "input"))
    )
    (net (code "49") (name "Net-(0-P)") (class "Default")
      (node (ref "0") (pin "1") (pinfunction "P_1") (pintype "passive"))
      (node (ref "IC25") (pin "11") (pinfunction "O_11") (pintype "output"))
    )
    (net (code "50") (name "Net-(1-P)") (class "Default")
      (node (ref "1") (pin "1") (pinfunction "P_1") (pintype "passive"))
      (node (ref "IC25") (pin "12") (pinfunction "I0_12") (pintype "input"))
      (node (ref "IC25") (pin "13") (pinfunction "I1_13") (pintype "input"))
      (node (ref "IC28") (pin "8") (pinfunction "O_8") (pintype "output"))
    )
    (net (code "51") (name "Net-(C5-Pad1)") (class "Default")
      (node (ref "C5") (pin "1") (pinfunction "1_1") (pintype "passive"))
      (node (ref "D5") (pin "C") (pinfunction "C_C") (pintype "passive"))
      (node (ref "R12") (pin "2") (pinfunction "2_2") (pintype "passive"))
      (node (ref "R14") (pin "1") (pinfunction "1_1") (pintype "passive"))
    )
    (net (code "52") (name "Net-(D3-PadA)") (class "Default")
      (node (ref "D3") (pin "A") (pinfunction "A_A") (pintype "passive"))
      (node (ref "R27") (pin "2") (pinfunction "2_2") (pintype "passive"))
    )
    (net (code "53") (name "Net-(H-P)") (class "Default")
      (node (ref "H") (pin "1") (pinfunction "P_1") (pintype "passive"))
      (node (ref "IC27") (pin "14") (pinfunction "O_14") (pintype "output"))
    )
    (net (code "54") (name "Net-(IC1B-I1)") (class "Default")
      (node (ref "IC1") (pin "10") (pinfunction "I1_10") (pintype "input"))
      (node (ref "IC6") (pin "2") (pinfunction "O_2") (pintype "output"))
    )
    (net (code "55") (name "Net-(IC1B-I2)") (class "Default")
      (node (ref "IC1") (pin "12") (pinfunction "I2_12") (pintype "input"))
      (node (ref "IC1") (pin "13") (pinfunction "I3_13") (pintype "input"))
      (node (ref "IC6") (pin "3") (pinfunction "O_3") (pintype "output"))
    )
    (net (code "56") (name "Net-(IC2A-I0)") (class "Default")
      (node (ref "IC2") (pin "2") (pinfunction "I0_2") (pintype "input"))
      (node (ref "IC2") (pin "3") (pinfunction "I1_3") (pintype "input"))
      (node (ref "IC3") (pin "6") (pinfunction "O_6") (pintype "output"))
    )
    (net (code "57") (name "Net-(IC2B-I0)") (class "Default")
      (node (ref "IC2") (pin "5") (pinfunction "I0_5") (pintype "input"))
      (node (ref "IC2") (pin "6") (pinfunction "I1_6") (pintype "input"))
      (node (ref "IC3") (pin "8") (pinfunction "O_8") (pintype "output"))
    )
    (net (code "58") (name "Net-(IC2C-O)") (class "Default")
      (node (ref "C39") (pin "1") (pinfunction "1_1") (pintype "passive"))
      (node (ref "D4") (pin "C") (pinfunction "C_C") (pintype "passive"))
      (node (ref "IC2") (pin "10") (pinfunction "O_10") (pintype "open_collector"))
      (node (ref "IC7") (pin "1") (pinfunction "I0_1") (pintype "input"))
      (node (ref "IC7") (pin "2") (pinfunction "I1_2") (pintype "input"))
      (node (ref "IC7") (pin "4") (pinfunction "I2_4") (pintype "input"))
      (node (ref "IC7") (pin "5") (pinfunction "I3_5") (pintype "input"))
      (node (ref "R26") (pin "1") (pinfunction "1_1") (pintype "passive"))
      (node (ref "R27") (pin "1") (pinfunction "1_1") (pintype "passive"))
    )
    (net (code "59") (name "Net-(IC6C-I0)") (class "Default")
      (node (ref "C25") (pin "1") (pinfunction "1_1") (pintype "passive"))
      (node (ref "IC6") (pin "9") (pinfunction "I0_9") (pintype "input"))
      (node (ref "R13") (pin "1") (pinfunction "1_1") (pintype "passive"))
    )
    (net (code "60") (name "Net-(IC6C-O)") (class "Default")
      (node (ref "C45") (pin "2") (pinfunction "2_2") (pintype "passive"))
      (node (ref "IC6") (pin "14") (pinfunction "O_14") (pintype "output"))
    )
    (net (code "61") (name "Net-(IC6D-I1)") (class "Default")
      (node (ref "C45") (pin "1") (pinfunction "1_1") (pintype "passive"))
      (node (ref "D5") (pin "A") (pinfunction "A_A") (pintype "passive"))
      (node (ref "IC6") (pin "12") (pinfunction "I1_12") (pintype "input"))
      (node (ref "R16") (pin "2") (pinfunction "2_2") (pintype "passive"))
    )
    (net (code "62") (name "Net-(IC7B-I2)") (class "Default")
      (node (ref "C40") (pin "1") (pinfunction "1_1") (pintype "passive"))
      (node (ref "IC7") (pin "12") (pinfunction "I2_12") (pintype "input"))
      (node (ref "IC7") (pin "13") (pinfunction "I3_13") (pintype "input"))
      (node (ref "R11") (pin "2") (pinfunction "2_2") (pintype "passive"))
    )
    (net (code "63") (name "Net-(IC9D-O)") (class "Default")
      (node (ref "IC9") (pin "8") (pinfunction "O_8") (pintype "output"))
      (node (ref "R11") (pin "1") (pinfunction "1_1") (pintype "passive"))
    )
    (net (code "64") (name "Net-(IC10A-O)") (class "Default")
      (node (ref "IC10") (pin "3") (pinfunction "O_3") (pintype "output"))
      (node (ref "IC10") (pin "4") (pinfunction "I0_4") (pintype "input"))
      (node (ref "IC10") (pin "5") (pinfunction "I1_5") (pintype "input"))
    )
    (net (code "65") (name "Net-(IC10B-O)") (class "Default")
      (node (ref "IC10") (pin "12") (pinfunction "I0_12") (pintype "input"))
      (node (ref "IC10") (pin "6") (pinfunction "O_6") (pintype "output"))
    )
    (net (code "66") (name "Net-(IC10C-I0)") (class "Default")
      (node (ref "IC1") (pin "8") (pinfunction "O_8") (pintype "output"))
      (node (ref "IC10") (pin "13") (pinfunction "I1_13") (pintype "input"))
      (node (ref "IC10") (pin "9") (pinfunction "I0_9") (pintype "input"))
    )
    (net (code "67") (name "Net-(IC10C-I1)") (class "Default")
      (node (ref "IC10") (pin "10") (pinfunction "I1_10") (pintype "input"))
      (node (ref "IC10") (pin "11") (pinfunction "O_11") (pintype "output"))
    )
    (net (code "68") (name "Net-(IC11A-CLR)") (class "Default")
      (node (ref "IC11") (pin "1") (pinfunction "CLR_1") (pintype "input"))
      (node (ref "R24") (pin "2") (pinfunction "2_2") (pintype "passive"))
      (node (ref "SET") (pin "1") (pinfunction "P_1") (pintype "passive"))
    )
    (net (code "69") (name "Net-(IC11A-PRE)") (class "Default")
      (node (ref "IC11") (pin "4") (pinfunction "PRE_4") (pintype "input"))
      (node (ref "R22") (pin "2") (pinfunction "2_2") (pintype "passive"))
      (node (ref "RES") (pin "1") (pinfunction "P_1") (pintype "passive"))
    )
    (net (code "70") (name "Net-(IC11A-Q)") (class "Default")
      (node (ref "IC11") (pin "5") (pinfunction "Q_5") (pintype "output"))
      (node (ref "IC7") (pin "10") (pinfunction "I1_10") (pintype "input"))
      (node (ref "IC7") (pin "9") (pinfunction "I0_9") (pintype "input"))
      (node (ref "IC9") (pin "9") (pinfunction "I_9") (pintype "input"))
    )
    (net (code "71") (name "Net-(IC11B-PRE)") (class "Default")
      (node (ref "IC11") (pin "10") (pinfunction "PRE_10") (pintype "input"))
      (node (ref "IC7") (pin "8") (pinfunction "O_8") (pintype "output"))
    )
    (net (code "72") (name "Net-(IC12A-I0)") (class "Default")
      (node (ref "IC12") (pin "2") (pinfunction "I0_2") (pintype "input"))
      (node (ref "IC12") (pin "3") (pinfunction "I1_3") (pintype "input"))
      (node (ref "IC8") (pin "11") (pinfunction "O_11") (pintype "output"))
    )
    (net (code "73") (name "Net-(IC12A-O)") (class "Default")
      (node (ref "IC12") (pin "1") (pinfunction "O_1") (pintype "open_collector"))
      (node (ref "R28") (pin "2") (pinfunction "2_2") (pintype "passive"))
      (node (ref "R6") (pin "2") (pinfunction "2_2") (pintype "passive"))
    )
    (net (code "74") (name "Net-(IC12C-I0)") (class "Default")
      (node (ref "IC12") (pin "8") (pinfunction "I0_8") (pintype "input"))
      (node (ref "IC12") (pin "9") (pinfunction "I1_9") (pintype "input"))
      (node (ref "IC8") (pin "6") (pinfunction "O_6") (pintype "output"))
    )
    (net (code "75") (name "Net-(IC12C-O)") (class "Default")
      (node (ref "IC12") (pin "10") (pinfunction "O_10") (pintype "open_collector"))
      (node (ref "R8") (pin "1") (pinfunction "1_1") (pintype "passive"))
      (node (ref "R9") (pin "1") (pinfunction "1_1") (pintype "passive"))
    )
    (net (code "76") (name "Net-(IC13A-O)") (class "Default")
      (node (ref "IC13") (pin "3") (pinfunction "O_3") (pintype "output"))
      (node (ref "R15") (pin "2") (pinfunction "2_2") (pintype "passive"))
    )
    (net (code "77") (name "Net-(IC14A-I0)") (class "Default")
      (node (ref "D3") (pin "C") (pinfunction "C_C") (pintype "passive"))
      (node (ref "IC14") (pin "1") (pinfunction "I0_1") (pintype "input"))
      (node (ref "IC14") (pin "2") (pinfunction "I1_2") (pintype "input"))
      (node (ref "IC2") (pin "8") (pinfunction "I0_8") (pintype "input"))
      (node (ref "IC7") (pin "6") (pinfunction "O_6") (pintype "output"))
      (node (ref "R26") (pin "2") (pinfunction "2_2") (pintype "passive"))
    )
    (net (code "78") (name "Net-(IC14B-O)") (class "Default")
      (node (ref "IC14") (pin "10") (pinfunction "I1_10") (pintype "input"))
      (node (ref "IC14") (pin "6") (pinfunction "O_6") (pintype "output"))
      (node (ref "IC14") (pin "9") (pinfunction "I0_9") (pintype "input"))
    )
    (net (code "79") (name "Net-(IC14C-O)") (class "Default")
      (node (ref "IC14") (pin "8") (pinfunction "O_8") (pintype "output"))
      (node (ref "IC17") (pin "14") (pinfunction "CKA_14") (pintype "input"))
    )
    (net (code "80") (name "Net-(IC15A-I1)") (class "Default")
      (node (ref "IC15") (pin "12") (pinfunction "I1_12") (pintype "input"))
      (node (ref "IC15") (pin "3") (pinfunction "I1_3") (pintype "input"))
      (node (ref "IC15") (pin "6") (pinfunction "I1_6") (pintype "input"))
      (node (ref "IC15") (pin "9") (pinfunction "I1_9") (pintype "input"))
      (node (ref "IC31") (pin "12") (pinfunction "I1_12") (pintype "input"))
      (node (ref "IC31") (pin "3") (pinfunction "I1_3") (pintype "input"))
      (node (ref "IC31") (pin "6") (pinfunction "I1_6") (pintype "input"))
      (node (ref "IC31") (pin "9") (pinfunction "I1_9") (pintype "input"))
      (node (ref "IC4") (pin "11") (pinfunction "I0_11") (pintype "input"))
      (node (ref "IC4") (pin "3") (pinfunction "I1_3") (pintype "input"))
      (node (ref "IC4") (pin "6") (pinfunction "I1_6") (pintype "input"))
      (node (ref "IC4") (pin "9") (pinfunction "I1_9") (pintype "input"))
      (node (ref "IC9") (pin "10") (pinfunction "O_10") (pintype "output"))
      (node (ref "IC9") (pin "12") (pinfunction "O_12") (pintype "output"))
    )
    (net (code "81") (name "Net-(IC19A-I0)") (class "Default")
      (node (ref "C4") (pin "1") (pinfunction "1_1") (pintype "passive"))
      (node (ref "IC19") (pin "1") (pinfunction "I0_1") (pintype "input"))
      (node (ref "IC19") (pin "2") (pinfunction "I1_2") (pintype "input"))
      (node (ref "R15") (pin "1") (pinfunction "1_1") (pintype "passive"))
    )
    (net (code "82") (name "Net-(IC19A-O)") (class "Default")
      (node (ref "IC19") (pin "6") (pinfunction "O_6") (pintype "output"))
      (node (ref "R4") (pin "1") (pinfunction "1_1") (pintype "passive"))
    )
    (net (code "83") (name "Net-(IC19B-O)") (class "Default")
      (node (ref "IC19") (pin "8") (pinfunction "O_8") (pintype "output"))
      (node (ref "IC9") (pin "11") (pinfunction "I_11") (pintype "input"))
      (node (ref "IC9") (pin "13") (pinfunction "I_13") (pintype "input"))
    )
    (net (code "84") (name "Net-(IC25A-I1)") (class "Default")
      (node (ref "IC25") (pin "2") (pinfunction "I1_2") (pintype "input"))
      (node (ref "IC27") (pin "2") (pinfunction "O_2") (pintype "output"))
    )
    (net (code "85") (name "Net-(IC25A-O)") (class "Default")
      (node (ref "IC25") (pin "3") (pinfunction "O_3") (pintype "output"))
      (node (ref "IC25") (pin "4") (pinfunction "I0_4") (pintype "input"))
    )
    (net (code "86") (name "Net-(IC26A-B1)") (class "Default")
      (node (ref "IC26") (pin "3") (pinfunction "B1_3") (pintype "input"))
      (node (ref "IC26") (pin "4") (pinfunction "B2_4") (pintype "input"))
      (node (ref "IC30") (pin "6") (pinfunction "O_6") (pintype "output"))
    )
    (net (code "87") (name "Net-(IC26A-C)") (class "Default")
      (node (ref "C41") (pin "2") (pinfunction "2_2") (pintype "passive"))
      (node (ref "IC26") (pin "11") (pinfunction "C_11") (pintype "input"))
    )
    (net (code "88") (name "Net-(IC26A-R{slash}C)") (class "Default")
      (node (ref "C41") (pin "1") (pinfunction "1_1") (pintype "passive"))
      (node (ref "IC26") (pin "13") (pinfunction "R/C_13") (pintype "input"))
      (node (ref "R17") (pin "2") (pinfunction "2_2") (pintype "passive"))
    )
    (net (code "89") (name "Net-(IC27A-O)") (class "Default")
      (node (ref "IC27") (pin "3") (pinfunction "O_3") (pintype "output"))
      (node (ref "R3") (pin "2") (pinfunction "2_2") (pintype "passive"))
    )
    (net (code "90") (name "Net-(IC27B-I0)") (class "Default")
      (node (ref "IC27") (pin "6") (pinfunction "I0_6") (pintype "input"))
      (node (ref "IC27") (pin "7") (pinfunction "I1_7") (pintype "input"))
      (node (ref "KS") (pin "1") (pinfunction "P_1") (pintype "passive"))
    )
    (net (code "91") (name "Net-(IC28A-I0)") (class "Default")
      (node (ref "C33") (pin "1") (pinfunction "1_1") (pintype "passive"))
      (node (ref "IC28") (pin "1") (pinfunction "I0_1") (pintype "input"))
      (node (ref "IC28") (pin "2") (pinfunction "I1_2") (pintype "input"))
      (node (ref "IC28") (pin "4") (pinfunction "I2_4") (pintype "input"))
      (node (ref "IC28") (pin "5") (pinfunction "I3_5") (pintype "input"))
      (node (ref "R4") (pin "2") (pinfunction "2_2") (pintype "passive"))
    )
    (net (code "92") (name "Net-(IC28A-O)") (class "Default")
      (node (ref "C25") (pin "2") (pinfunction "2_2") (pintype "passive"))
      (node (ref "IC28") (pin "6") (pinfunction "O_6") (pintype "output"))
    )
    (net (code "93") (name "Net-(IC28B-I0)") (class "Default")
      (node (ref "D2") (pin "C") (pinfunction "C_C") (pintype "passive"))
      (node (ref "IC28") (pin "10") (pinfunction "I1_10") (pintype "input"))
      (node (ref "IC28") (pin "12") (pinfunction "I2_12") (pintype "input"))
      (node (ref "IC28") (pin "13") (pinfunction "I3_13") (pintype "input"))
      (node (ref "IC28") (pin "9") (pinfunction "I0_9") (pintype "input"))
      (node (ref "Q2") (pin "1") (pinfunction "E_1") (pintype "passive"))
      (node (ref "R1") (pin "2") (pinfunction "2_2") (pintype "passive"))
    )
    (net (code "94") (name "Net-(IC29A-C)") (class "Default")
      (node (ref "C44") (pin "2") (pinfunction "2_2") (pintype "passive"))
      (node (ref "IC29") (pin "11") (pinfunction "C_11") (pintype "input"))
    )
    (net (code "95") (name "Net-(IC29A-Q)") (class "Default")
      (node (ref "IC29") (pin "8") (pinfunction "Q_8") (pintype "output"))
      (node (ref "IC33") (pin "1") (pinfunction "A1_1") (pintype "input"))
      (node (ref "IC33") (pin "2") (pinfunction "A2_2") (pintype "input"))
    )
    (net (code "96") (name "Net-(IC29A-R{slash}C)") (class "Default")
      (node (ref "C44") (pin "1") (pinfunction "1_1") (pintype "passive"))
      (node (ref "IC29") (pin "13") (pinfunction "R/C_13") (pintype "input"))
      (node (ref "R21") (pin "2") (pinfunction "2_2") (pintype "passive"))
    )
    (net (code "97") (name "Net-(IC33A-B1)") (class "Default")
      (node (ref "C43") (pin "1") (pinfunction "1_1") (pintype "passive"))
      (node (ref "IC33") (pin "3") (pinfunction "B1_3") (pintype "input"))
      (node (ref "IC33") (pin "4") (pinfunction "B2_4") (pintype "input"))
      (node (ref "R19") (pin "1") (pinfunction "1_1") (pintype "passive"))
      (node (ref "R23") (pin "2") (pinfunction "2_2") (pintype "passive"))
    )
    (net (code "98") (name "Net-(IC33A-C)") (class "Default")
      (node (ref "C42") (pin "2") (pinfunction "2_2") (pintype "passive"))
      (node (ref "IC33") (pin "11") (pinfunction "C_11") (pintype "input"))
    )
    (net (code "99") (name "Net-(IC33A-R{slash}C)") (class "Default")
      (node (ref "C42") (pin "1") (pinfunction "1_1") (pintype "passive"))
      (node (ref "IC33") (pin "13") (pinfunction "R/C_13") (pintype "input"))
      (node (ref "R25") (pin "2") (pinfunction "2_2") (pintype "passive"))
    )
    (net (code "100") (name "Net-(Q1-B)") (class "Default")
      (node (ref "Q1") (pin "2") (pinfunction "B_2") (pintype "passive"))
      (node (ref "R8") (pin "2") (pinfunction "2_2") (pintype "passive"))
    )
    (net (code "101") (name "Net-(Q1-C)") (class "Default")
      (node (ref "Q1") (pin "3") (pinfunction "C_3") (pintype "passive"))
      (node (ref "R10") (pin "1") (pinfunction "1_1") (pintype "passive"))
    )
    (net (code "102") (name "Net-(Q2-B)") (class "Default")
      (node (ref "C7") (pin "+") (pinfunction "+_+") (pintype "passive"))
      (node (ref "Q2") (pin "2") (pinfunction "B_2") (pintype "passive"))
      (node (ref "R3") (pin "1") (pinfunction "1_1") (pintype "passive"))
    )
    (net (code "103") (name "Net-(Q2-C)") (class "Default")
      (node (ref "Q2") (pin "3") (pinfunction "C_3") (pintype "passive"))
      (node (ref "R2") (pin "1") (pinfunction "1_1") (pintype "passive"))
    )
    (net (code "104") (name "Net-(Q3-B)") (class "Default")
      (node (ref "Q3") (pin "2") (pinfunction "B_2") (pintype "passive"))
      (node (ref "R6") (pin "1") (pinfunction "1_1") (pintype "passive"))
    )
    (net (code "105") (name "Net-(Q3-C)") (class "Default")
      (node (ref "Q3") (pin "3") (pinfunction "C_3") (pintype "passive"))
      (node (ref "R5") (pin "2") (pinfunction "2_2") (pintype "passive"))
    )
    (net (code "106") (name "Net-(U$2AU-1)") (class "Default")
      (node (ref "U$2") (pin "BF1") (pinfunction "1_BF1") (pintype "bidirectional"))
      (node (ref "U$2") (pin "BN1") (pinfunction "1_BN1") (pintype "bidirectional"))
    )
    (net (code "107") (name "Net-(U$2CZ-1)") (class "Default")
      (node (ref "U$2") (pin "CT2") (pinfunction "1_CT2") (pintype "bidirectional"))
      (node (ref "U$2") (pin "DF2") (pinfunction "1_DF2") (pintype "bidirectional"))
      (node (ref "U$2") (pin "DN2") (pinfunction "1_DN2") (pintype "bidirectional"))
    )
    (net (code "108") (name "Net-(U$2D-1)") (class "Default")
      (node (ref "R7") (pin "1") (pinfunction "1_1") (pintype "passive"))
      (node (ref "U$2") (pin "AB2") (pinfunction "1_AB2") (pintype "bidirectional"))
    )
    (net (code "109") (name "Net-(U$2DO-1)") (class "Default")
      (node (ref "U$2") (pin "DF1") (pinfunction "1_DF1") (pintype "bidirectional"))
      (node (ref "U$2") (pin "DN1") (pinfunction "1_DN1") (pintype "bidirectional"))
    )
    (net (code "110") (name "Net-(U$2K-1)") (class "Default")
      (node (ref "U$2") (pin "AF1") (pinfunction "1_AF1") (pintype "bidirectional"))
      (node (ref "U$2") (pin "AN1") (pinfunction "1_AN1") (pintype "bidirectional"))
    )
    (net (code "111") (name "ODD") (class "Default")
      (node (ref "IC2") (pin "1") (pinfunction "O_1") (pintype "open_collector"))
      (node (ref "IC22") (pin "13") (pinfunction "C12_13") (pintype "input"))
      (node (ref "IC22") (pin "4") (pinfunction "C34_4") (pintype "input"))
      (node (ref "IC29") (pin "3") (pinfunction "B1_3") (pintype "input"))
      (node (ref "IC29") (pin "4") (pinfunction "B2_4") (pintype "input"))
      (node (ref "IC32") (pin "13") (pinfunction "C12_13") (pintype "input"))
      (node (ref "IC32") (pin "4") (pinfunction "C34_4") (pintype "input"))
      (node (ref "R20") (pin "2") (pinfunction "2_2") (pintype "passive"))
    )
    (net (code "112") (name "PULSE") (class "Default")
      (node (ref "IC12") (pin "5") (pinfunction "I0_5") (pintype "input"))
      (node (ref "IC6") (pin "10") (pinfunction "I1_10") (pintype "input"))
      (node (ref "IC6") (pin "13") (pinfunction "O_13") (pintype "output"))
      (node (ref "IC8") (pin "13") (pinfunction "I1_13") (pintype "input"))
      (node (ref "IC8") (pin "5") (pinfunction "I1_5") (pintype "input"))
    )
    (net (code "113") (name "PULSE_LA") (class "Default")
      (node (ref "Q3") (pin "1") (pinfunction "E_1") (pintype "passive"))
      (node (ref "U$2") (pin "DR2") (pinfunction "1_DR2") (pintype "bidirectional"))
    )
    (net (code "114") (name "RUNL") (class "Default")
      (node (ref "IC10") (pin "2") (pinfunction "I1_2") (pintype "input"))
      (node (ref "IC13") (pin "2") (pinfunction "O_2") (pintype "output"))
      (node (ref "IC13") (pin "4") (pinfunction "I0_4") (pintype "input"))
      (node (ref "IC13") (pin "5") (pinfunction "I1_5") (pintype "input"))
    )
    (net (code "115") (name "SWITCH") (class "Default")
      (node (ref "IC27") (pin "4") (pinfunction "I0_4") (pintype "input"))
      (node (ref "IC27") (pin "5") (pinfunction "I1_5") (pintype "input"))
      (node (ref "N") (pin "1") (pinfunction "P_1") (pintype "passive"))
      (node (ref "U$2") (pin "DV2") (pinfunction "1_DV2") (pintype "bidirectional"))
    )
    (net (code "116") (name "TIMER1") (class "Default")
      (node (ref "IC25") (pin "8") (pinfunction "O_8") (pintype "output"))
      (node (ref "IC30") (pin "10") (pinfunction "I1_10") (pintype "input"))
      (node (ref "IC30") (pin "9") (pinfunction "I0_9") (pintype "input"))
    )
    (net (code "117") (name "TIMER2") (class "Default")
      (node (ref "IC30") (pin "4") (pinfunction "I2_4") (pintype "input"))
      (node (ref "IC33") (pin "8") (pinfunction "Q_8") (pintype "output"))
      (node (ref "IC34") (pin "12") (pinfunction "I2_12") (pintype "input"))
      (node (ref "IC34") (pin "4") (pinfunction "I2_4") (pintype "input"))
    )
    (net (code "118") (name "TP4") (class "Default")
      (node (ref "IC6") (pin "6") (pinfunction "I0_6") (pintype "input"))
      (node (ref "U$2") (pin "CJ2") (pinfunction "1_CJ2") (pintype "bidirectional"))
    )
    (net (code "119") (name "TS4L") (class "Default")
      (node (ref "IC13") (pin "13") (pinfunction "O_13") (pintype "output"))
      (node (ref "IC19") (pin "12") (pinfunction "I2_12") (pintype "input"))
      (node (ref "IC19") (pin "13") (pinfunction "I3_13") (pintype "input"))
    )
    (net (code "120") (name "VCC") (class "Default")
      (node (ref "C1") (pin "1") (pinfunction "1_1") (pintype "passive"))
      (node (ref "C11") (pin "1") (pinfunction "1_1") (pintype "passive"))
      (node (ref "C12") (pin "1") (pinfunction "1_1") (pintype "passive"))
      (node (ref "C15") (pin "1") (pinfunction "1_1") (pintype "passive"))
      (node (ref "C16") (pin "1") (pinfunction "1_1") (pintype "passive"))
      (node (ref "C18") (pin "1") (pinfunction "1_1") (pintype "passive"))
      (node (ref "C2") (pin "1") (pinfunction "1_1") (pintype "passive"))
      (node (ref "C21") (pin "1") (pinfunction "1_1") (pintype "passive"))
      (node (ref "C24") (pin "1") (pinfunction "1_1") (pintype "passive"))
      (node (ref "C28") (pin "1") (pinfunction "1_1") (pintype "passive"))
      (node (ref "C29") (pin "1") (pinfunction "1_1") (pintype "passive"))
      (node (ref "C3") (pin "1") (pinfunction "1_1") (pintype "passive"))
      (node (ref "C31") (pin "1") (pinfunction "1_1") (pintype "passive"))
      (node (ref "C32") (pin "1") (pinfunction "1_1") (pintype "passive"))
      (node (ref "C34") (pin "+") (pinfunction "+_+") (pintype "passive"))
      (node (ref "C35") (pin "+") (pinfunction "+_+") (pintype "passive"))
      (node (ref "C36") (pin "+") (pinfunction "+_+") (pintype "passive"))
      (node (ref "C6") (pin "1") (pinfunction "1_1") (pintype "passive"))
      (node (ref "IC20") (pin "12") (pinfunction "VCC1_12") (pintype "input"))
      (node (ref "IC20") (pin "13") (pinfunction "P_13") (pintype "input"))
      (node (ref "IC20") (pin "15") (pinfunction "VBB_15") (pintype "input"))
      (node (ref "IC20") (pin "22") (pinfunction "VCC2_22") (pintype "input"))
      (node (ref "IC20") (pin "23") (pinfunction "VCC3_23") (pintype "input"))
      (node (ref "R10") (pin "2") (pinfunction "2_2") (pintype "passive"))
      (node (ref "R12") (pin "1") (pinfunction "1_1") (pintype "passive"))
      (node (ref "R16") (pin "1") (pinfunction "1_1") (pintype "passive"))
      (node (ref "R17") (pin "1") (pinfunction "1_1") (pintype "passive"))
      (node (ref "R18") (pin "1") (pinfunction "1_1") (pintype "passive"))
      (node (ref "R2") (pin "2") (pinfunction "2_2") (pintype "passive"))
      (node (ref "R20") (pin "1") (pinfunction "1_1") (pintype "passive"))
      (node (ref "R21") (pin "1") (pinfunction "1_1") (pintype "passive"))
      (node (ref "R22") (pin "1") (pinfunction "1_1") (pintype "passive"))
      (node (ref "R23") (pin "1") (pinfunction "1_1") (pintype "passive"))
      (node (ref "R24") (pin "1") (pinfunction "1_1") (pintype "passive"))
      (node (ref "R25") (pin "1") (pinfunction "1_1") (pintype "passive"))
      (node (ref "R28") (pin "1") (pinfunction "1_1") (pintype "passive"))
      (node (ref "R5") (pin "1") (pinfunction "1_1") (pintype "passive"))
      (node (ref "R9") (pin "2") (pinfunction "2_2") (pintype "passive"))
      (node (ref "U$2") (pin "AA2") (pinfunction "1_AA2") (pintype "bidirectional"))
      (node (ref "U$2") (pin "BA2") (pinfunction "1_BA2") (pintype "bidirectional"))
      (node (ref "U$2") (pin "CA2") (pinfunction "1_CA2") (pintype "bidirectional"))
    )
    (net (code "121") (name "VDD") (class "Default")
      (node (ref "C19") (pin "2") (pinfunction "2_2") (pintype "passive"))
      (node (ref "C37") (pin "-") (pinfunction "-_-") (pintype "passive"))
      (node (ref "D1") (pin "A") (pinfunction "A_A") (pintype "passive"))
      (node (ref "IC20") (pin "16") (pinfunction "VGG_16") (pintype "input"))
      (node (ref "IC20") (pin "24") (pinfunction "VDD_24") (pintype "input"))
      (node (ref "R7") (pin "2") (pinfunction "2_2") (pintype "passive"))
    )
    (net (code "122") (name "unconnected-(IC5A-Q1-Pad16)") (class "Default")
      (node (ref "IC5") (pin "16") (pinfunction "Q1_16") (pintype "output"))
    )
    (net (code "123") (name "unconnected-(IC5A-Q2-Pad15)") (class "Default")
      (node (ref "IC5") (pin "15") (pinfunction "Q2_15") (pintype "output"))
    )
    (net (code "124") (name "unconnected-(IC5A-Q3-Pad10)") (class "Default")
      (node (ref "IC5") (pin "10") (pinfunction "Q3_10") (pintype "output"))
    )
    (net (code "125") (name "unconnected-(IC5A-Q4-Pad9)") (class "Default")
      (node (ref "IC5") (pin "9") (pinfunction "Q4_9") (pintype "output"))
    )
    (net (code "126") (name "unconnected-(IC11A-~{Q}-Pad6)") (class "Default")
      (node (ref "IC11") (pin "6") (pinfunction "~{Q}_6") (pintype "output"))
    )
    (net (code "127") (name "unconnected-(IC16A-Q1-Pad16)") (class "Default")
      (node (ref "IC16") (pin "16") (pinfunction "Q1_16") (pintype "output"))
    )
    (net (code "128") (name "unconnected-(IC16A-Q2-Pad15)") (class "Default")
      (node (ref "IC16") (pin "15") (pinfunction "Q2_15") (pintype "output"))
    )
    (net (code "129") (name "unconnected-(IC16A-Q3-Pad10)") (class "Default")
      (node (ref "IC16") (pin "10") (pinfunction "Q3_10") (pintype "output"))
    )
    (net (code "130") (name "unconnected-(IC16A-Q4-Pad9)") (class "Default")
      (node (ref "IC16") (pin "9") (pinfunction "Q4_9") (pintype "output"))
    )
    (net (code "131") (name "unconnected-(IC22A-Q1-Pad16)") (class "Default")
      (node (ref "IC22") (pin "16") (pinfunction "Q1_16") (pintype "output"))
    )
    (net (code "132") (name "unconnected-(IC22A-Q2-Pad15)") (class "Default")
      (node (ref "IC22") (pin "15") (pinfunction "Q2_15") (pintype "output"))
    )
    (net (code "133") (name "unconnected-(IC22A-Q3-Pad10)") (class "Default")
      (node (ref "IC22") (pin "10") (pinfunction "Q3_10") (pintype "output"))
    )
    (net (code "134") (name "unconnected-(IC22A-Q4-Pad9)") (class "Default")
      (node (ref "IC22") (pin "9") (pinfunction "Q4_9") (pintype "output"))
    )
    (net (code "135") (name "unconnected-(IC26A-Q-Pad8)") (class "Default")
      (node (ref "IC26") (pin "8") (pinfunction "Q_8") (pintype "output"))
    )
    (net (code "136") (name "unconnected-(IC32A-Q1-Pad16)") (class "Default")
      (node (ref "IC32") (pin "16") (pinfunction "Q1_16") (pintype "output"))
    )
    (net (code "137") (name "unconnected-(IC32A-Q2-Pad15)") (class "Default")
      (node (ref "IC32") (pin "15") (pinfunction "Q2_15") (pintype "output"))
    )
    (net (code "138") (name "unconnected-(IC32A-Q3-Pad10)") (class "Default")
      (node (ref "IC32") (pin "10") (pinfunction "Q3_10") (pintype "output"))
    )
    (net (code "139") (name "unconnected-(IC32A-Q4-Pad9)") (class "Default")
      (node (ref "IC32") (pin "9") (pinfunction "Q4_9") (pintype "output"))
    )
    (net (code "140") (name "unconnected-(IC33A-~{Q}-Pad6)") (class "Default")
      (node (ref "IC33") (pin "6") (pinfunction "~{Q}_6") (pintype "output"))
    )
    (net (code "141") (name "~{A0}") (class "Default")
      (node (ref "IC3") (pin "12") (pinfunction "I2_12") (pintype "input"))
      (node (ref "IC3") (pin "13") (pinfunction "I3_13") (pintype "input"))
      (node (ref "IC9") (pin "6") (pinfunction "O_6") (pintype "output"))
    )
    (net (code "142") (name "~{BRK_DATA_CONT}") (class "Default")
      (node (ref "IC12") (pin "13") (pinfunction "O_13") (pintype "open_collector"))
      (node (ref "U$2") (pin "BK2") (pinfunction "1_BK2") (pintype "bidirectional"))
    )
    (net (code "143") (name "~{CS}") (class "Default")
      (node (ref "IC14") (pin "11") (pinfunction "O_11") (pintype "output"))
      (node (ref "IC20") (pin "14") (pinfunction "~{CS}_14") (pintype "input"))
    )
    (net (code "144") (name "~{D0}") (class "Default")
      (node (ref "IC16") (pin "7") (pinfunction "D4_7") (pintype "input"))
      (node (ref "IC22") (pin "7") (pinfunction "D4_7") (pintype "input"))
      (node (ref "IC23") (pin "2") (pinfunction "O_2") (pintype "output"))
    )
    (net (code "145") (name "~{D1}") (class "Default")
      (node (ref "IC16") (pin "6") (pinfunction "D3_6") (pintype "input"))
      (node (ref "IC22") (pin "6") (pinfunction "D3_6") (pintype "input"))
      (node (ref "IC23") (pin "4") (pinfunction "O_4") (pintype "output"))
    )
    (net (code "146") (name "~{D2}") (class "Default")
      (node (ref "IC16") (pin "3") (pinfunction "D2_3") (pintype "input"))
      (node (ref "IC22") (pin "3") (pinfunction "D2_3") (pintype "input"))
      (node (ref "IC23") (pin "6") (pinfunction "O_6") (pintype "output"))
    )
    (net (code "147") (name "~{D3}") (class "Default")
      (node (ref "IC16") (pin "2") (pinfunction "D1_2") (pintype "input"))
      (node (ref "IC22") (pin "2") (pinfunction "D1_2") (pintype "input"))
      (node (ref "IC23") (pin "8") (pinfunction "O_8") (pintype "output"))
    )
    (net (code "148") (name "~{D4}") (class "Default")
      (node (ref "IC23") (pin "10") (pinfunction "O_10") (pintype "output"))
      (node (ref "IC32") (pin "7") (pinfunction "D4_7") (pintype "input"))
      (node (ref "IC5") (pin "7") (pinfunction "D4_7") (pintype "input"))
    )
    (net (code "149") (name "~{D5}") (class "Default")
      (node (ref "IC23") (pin "12") (pinfunction "O_12") (pintype "output"))
      (node (ref "IC32") (pin "6") (pinfunction "D3_6") (pintype "input"))
      (node (ref "IC5") (pin "6") (pinfunction "D3_6") (pintype "input"))
    )
    (net (code "150") (name "~{D6}") (class "Default")
      (node (ref "IC32") (pin "3") (pinfunction "D2_3") (pintype "input"))
      (node (ref "IC5") (pin "3") (pinfunction "D2_3") (pintype "input"))
      (node (ref "IC9") (pin "2") (pinfunction "O_2") (pintype "output"))
    )
    (net (code "151") (name "~{D7}") (class "Default")
      (node (ref "IC32") (pin "2") (pinfunction "D1_2") (pintype "input"))
      (node (ref "IC5") (pin "2") (pinfunction "D1_2") (pintype "input"))
      (node (ref "IC9") (pin "4") (pinfunction "O_4") (pintype "output"))
    )
    (net (code "152") (name "~{DATA0}") (class "Default")
      (node (ref "IC4") (pin "13") (pinfunction "O_13") (pintype "open_collector"))
      (node (ref "U$2") (pin "AR1") (pinfunction "1_AR1") (pintype "bidirectional"))
    )
    (net (code "153") (name "~{DATA1}") (class "Default")
      (node (ref "IC4") (pin "10") (pinfunction "O_10") (pintype "open_collector"))
      (node (ref "U$2") (pin "AS1") (pinfunction "1_AS1") (pintype "bidirectional"))
    )
    (net (code "154") (name "~{DATA2}") (class "Default")
      (node (ref "IC4") (pin "4") (pinfunction "O_4") (pintype "open_collector"))
      (node (ref "U$2") (pin "AU1") (pinfunction "1_AU1") (pintype "bidirectional"))
    )
    (net (code "155") (name "~{DATA3}") (class "Default")
      (node (ref "IC4") (pin "1") (pinfunction "O_1") (pintype "open_collector"))
      (node (ref "U$2") (pin "AV1") (pinfunction "1_AV1") (pintype "bidirectional"))
    )
    (net (code "156") (name "~{DATA4}") (class "Default")
      (node (ref "IC15") (pin "13") (pinfunction "O_13") (pintype "open_collector"))
      (node (ref "U$2") (pin "BR1") (pinfunction "1_BR1") (pintype "bidirectional"))
    )
    (net (code "157") (name "~{DATA5}") (class "Default")
      (node (ref "IC15") (pin "10") (pinfunction "O_10") (pintype "open_collector"))
      (node (ref "U$2") (pin "BS1") (pinfunction "1_BS1") (pintype "bidirectional"))
    )
    (net (code "158") (name "~{DATA6}") (class "Default")
      (node (ref "IC15") (pin "4") (pinfunction "O_4") (pintype "open_collector"))
      (node (ref "U$2") (pin "BU1") (pinfunction "1_BU1") (pintype "bidirectional"))
    )
    (net (code "159") (name "~{DATA7}") (class "Default")
      (node (ref "IC15") (pin "1") (pinfunction "O_1") (pintype "open_collector"))
      (node (ref "U$2") (pin "BV1") (pinfunction "1_BV1") (pintype "bidirectional"))
    )
    (net (code "160") (name "~{DATA8}") (class "Default")
      (node (ref "IC31") (pin "13") (pinfunction "O_13") (pintype "open_collector"))
      (node (ref "U$2") (pin "DR1") (pinfunction "1_DR1") (pintype "bidirectional"))
    )
    (net (code "161") (name "~{DATA9}") (class "Default")
      (node (ref "IC31") (pin "10") (pinfunction "O_10") (pintype "open_collector"))
      (node (ref "U$2") (pin "DS1") (pinfunction "1_DS1") (pintype "bidirectional"))
    )
    (net (code "162") (name "~{DATA10}") (class "Default")
      (node (ref "IC31") (pin "4") (pinfunction "O_4") (pintype "open_collector"))
      (node (ref "U$2") (pin "DU1") (pinfunction "1_DU1") (pintype "bidirectional"))
    )
    (net (code "163") (name "~{DATA11}") (class "Default")
      (node (ref "IC31") (pin "1") (pinfunction "O_1") (pintype "open_collector"))
      (node (ref "U$2") (pin "DV1") (pinfunction "1_DV1") (pintype "bidirectional"))
    )
    (net (code "164") (name "~{DOF0}") (class "Default")
      (node (ref "IC1") (pin "1") (pinfunction "I0_1") (pintype "input"))
      (node (ref "IC21") (pin "10") (pinfunction "I1_10") (pintype "input"))
      (node (ref "IC21") (pin "4") (pinfunction "I0_4") (pintype "input"))
      (node (ref "IC21") (pin "9") (pinfunction "I0_9") (pintype "input"))
      (node (ref "IC34") (pin "6") (pinfunction "O_6") (pintype "output"))
    )
    (net (code "165") (name "~{DOF1}") (class "Default")
      (node (ref "IC1") (pin "2") (pinfunction "I1_2") (pintype "input"))
      (node (ref "IC21") (pin "1") (pinfunction "I0_1") (pintype "input"))
      (node (ref "IC21") (pin "2") (pinfunction "I1_2") (pintype "input"))
      (node (ref "IC21") (pin "5") (pinfunction "I1_5") (pintype "input"))
      (node (ref "IC34") (pin "8") (pinfunction "O_8") (pintype "output"))
      (node (ref "IC8") (pin "9") (pinfunction "I0_9") (pintype "input"))
    )
    (net (code "166") (name "~{DOF2}") (class "Default")
      (node (ref "IC1") (pin "5") (pinfunction "I3_5") (pintype "input"))
      (node (ref "IC30") (pin "8") (pinfunction "O_8") (pintype "output"))
      (node (ref "IC8") (pin "1") (pinfunction "I0_1") (pintype "input"))
      (node (ref "IC8") (pin "2") (pinfunction "I1_2") (pintype "input"))
    )
    (net (code "167") (name "~{KEY_CONT}") (class "Default")
      (node (ref "IC18") (pin "4") (pinfunction "O_4") (pintype "open_collector"))
      (node (ref "U$2") (pin "DU2") (pinfunction "1_DU2") (pintype "bidirectional"))
    )
    (net (code "168") (name "~{LA_ENABLE}") (class "Default")
      (node (ref "IC18") (pin "1") (pinfunction "O_1") (pintype "open_collector"))
      (node (ref "U$2") (pin "BM2") (pinfunction "1_BM2") (pintype "bidirectional"))
    )
    (net (code "169") (name "~{MD_DIR}") (class "Default")
      (node (ref "IC18") (pin "13") (pinfunction "O_13") (pintype "open_collector"))
      (node (ref "U$2") (pin "AK2") (pinfunction "1_AK2") (pintype "bidirectional"))
    )
    (net (code "170") (name "~{MEM_START}") (class "Default")
      (node (ref "IC12") (pin "4") (pinfunction "O_4") (pintype "open_collector"))
      (node (ref "U$2") (pin "AJ2") (pinfunction "1_AJ2") (pintype "bidirectional"))
    )
    (net (code "171") (name "~{MS_DISABLE}") (class "Default")
      (node (ref "IC18") (pin "10") (pinfunction "O_10") (pintype "open_collector"))
      (node (ref "U$2") (pin "CV1") (pinfunction "1_CV1") (pintype "bidirectional"))
    )
    (net (code "172") (name "~{RUN}") (class "Default")
      (node (ref "IC13") (pin "6") (pinfunction "I0_6") (pintype "input"))
      (node (ref "U$2") (pin "BU2") (pinfunction "1_BU2") (pintype "bidirectional"))
    )
    (net (code "173") (name "~{STOP}") (class "Default")
      (node (ref "IC2") (pin "13") (pinfunction "O_13") (pintype "open_collector"))
      (node (ref "U$2") (pin "DS2") (pinfunction "1_DS2") (pintype "bidirectional"))
    )
    (net (code "174") (name "~{TIMER1}") (class "Default")
      (node (ref "IC25") (pin "10") (pinfunction "I1_10") (pintype "input"))
      (node (ref "IC25") (pin "9") (pinfunction "I0_9") (pintype "input"))
      (node (ref "IC29") (pin "6") (pinfunction "~{Q}_6") (pintype "output"))
    )
    (net (code "175") (name "~{TIMER3}") (class "Default")
      (node (ref "IC1") (pin "4") (pinfunction "I2_4") (pintype "input"))
      (node (ref "IC11") (pin "13") (pinfunction "CLR_13") (pintype "input"))
      (node (ref "IC26") (pin "6") (pinfunction "~{Q}_6") (pintype "output"))
      (node (ref "IC8") (pin "10") (pinfunction "I1_10") (pintype "input"))
    )
    (net (code "176") (name "~{TS4}") (class "Default")
      (node (ref "IC13") (pin "11") (pinfunction "I0_11") (pintype "input"))
      (node (ref "U$2") (pin "CP2") (pinfunction "1_CP2") (pintype "bidirectional"))
    )
  )
)
